# BatteryChargerCombiner.net
KiCad netlist of a schematic drawn in EAGLE
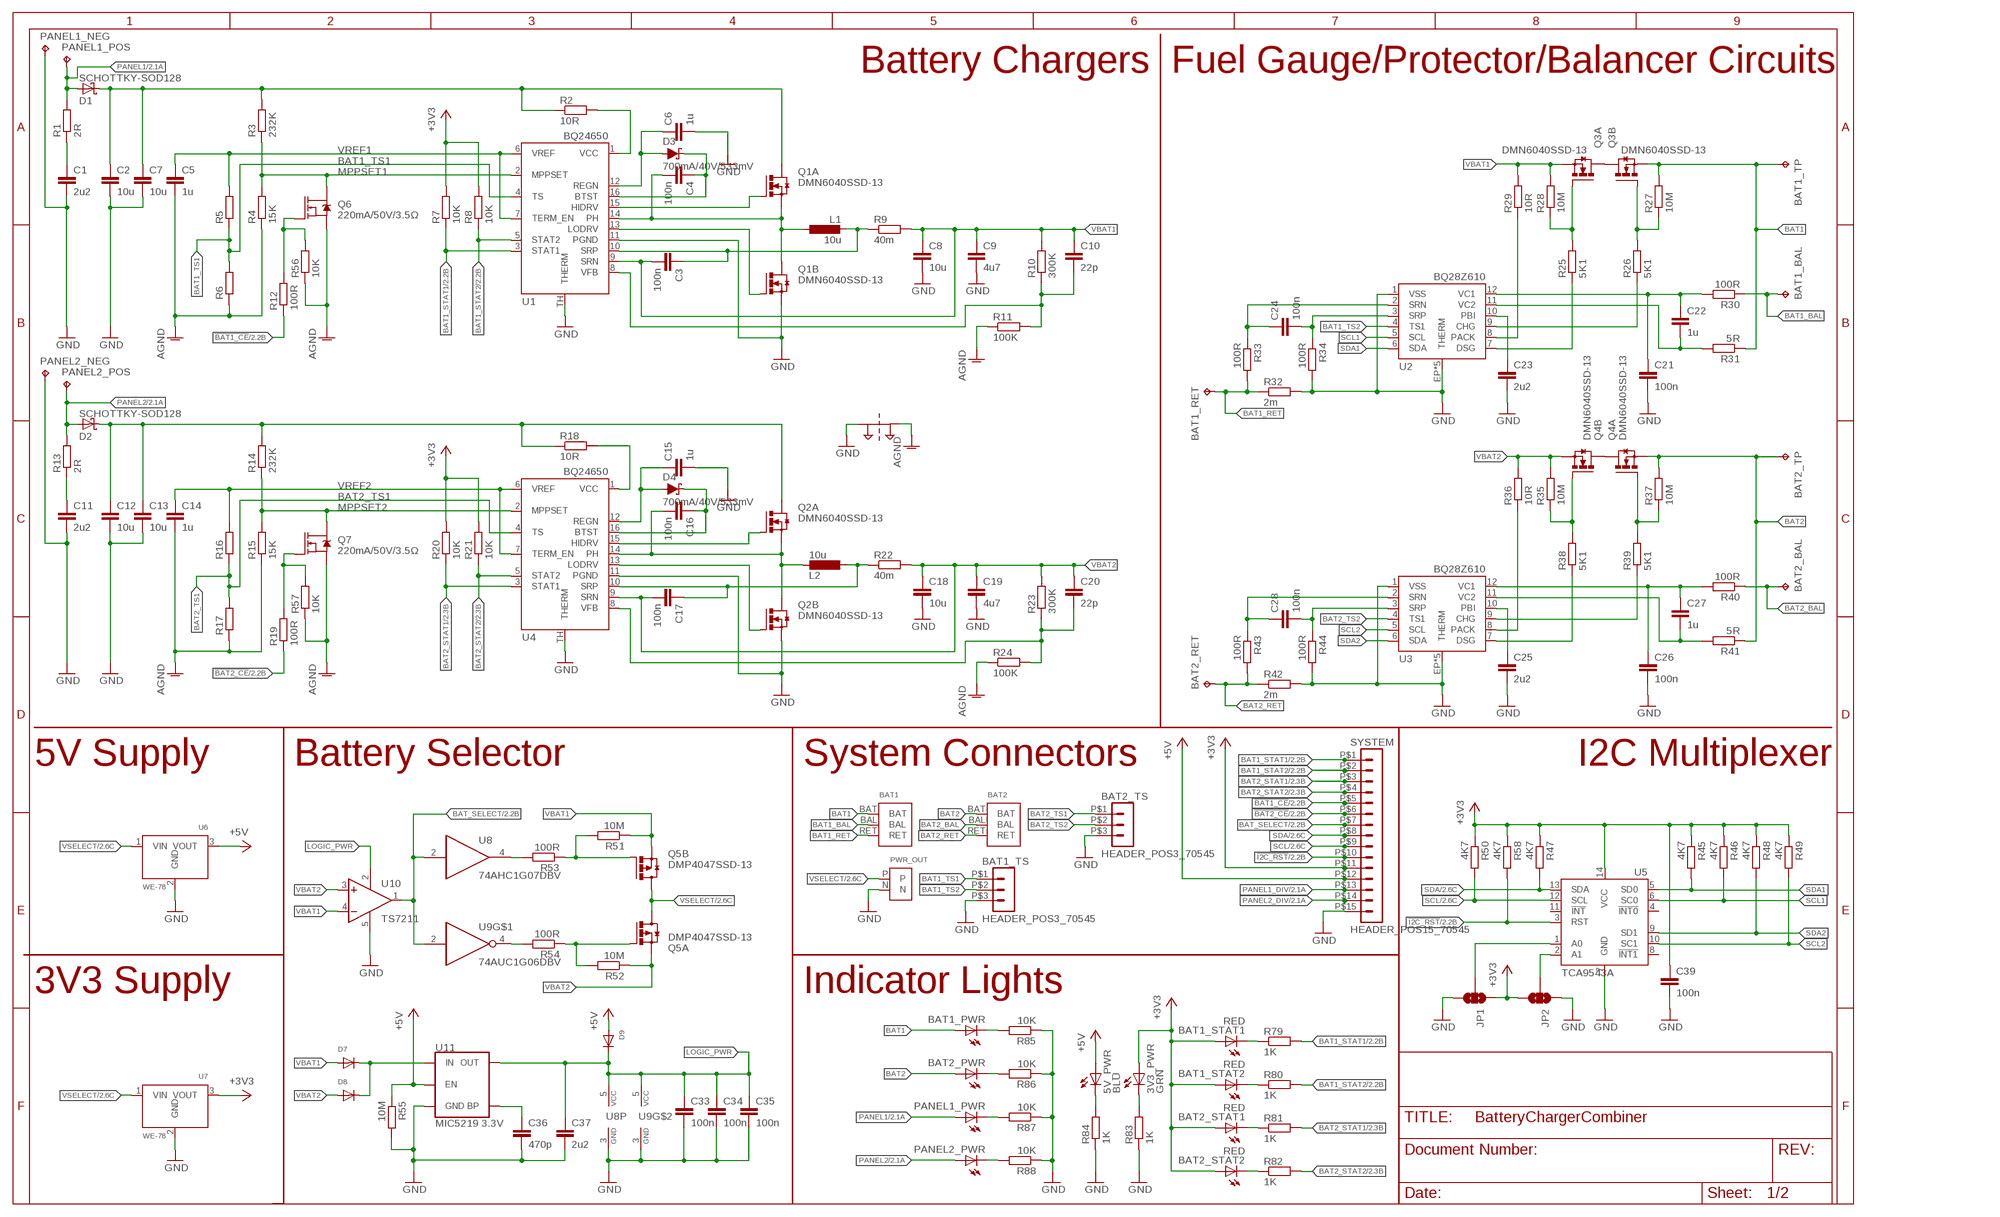
[diagram p0: schematic, sheet 1]
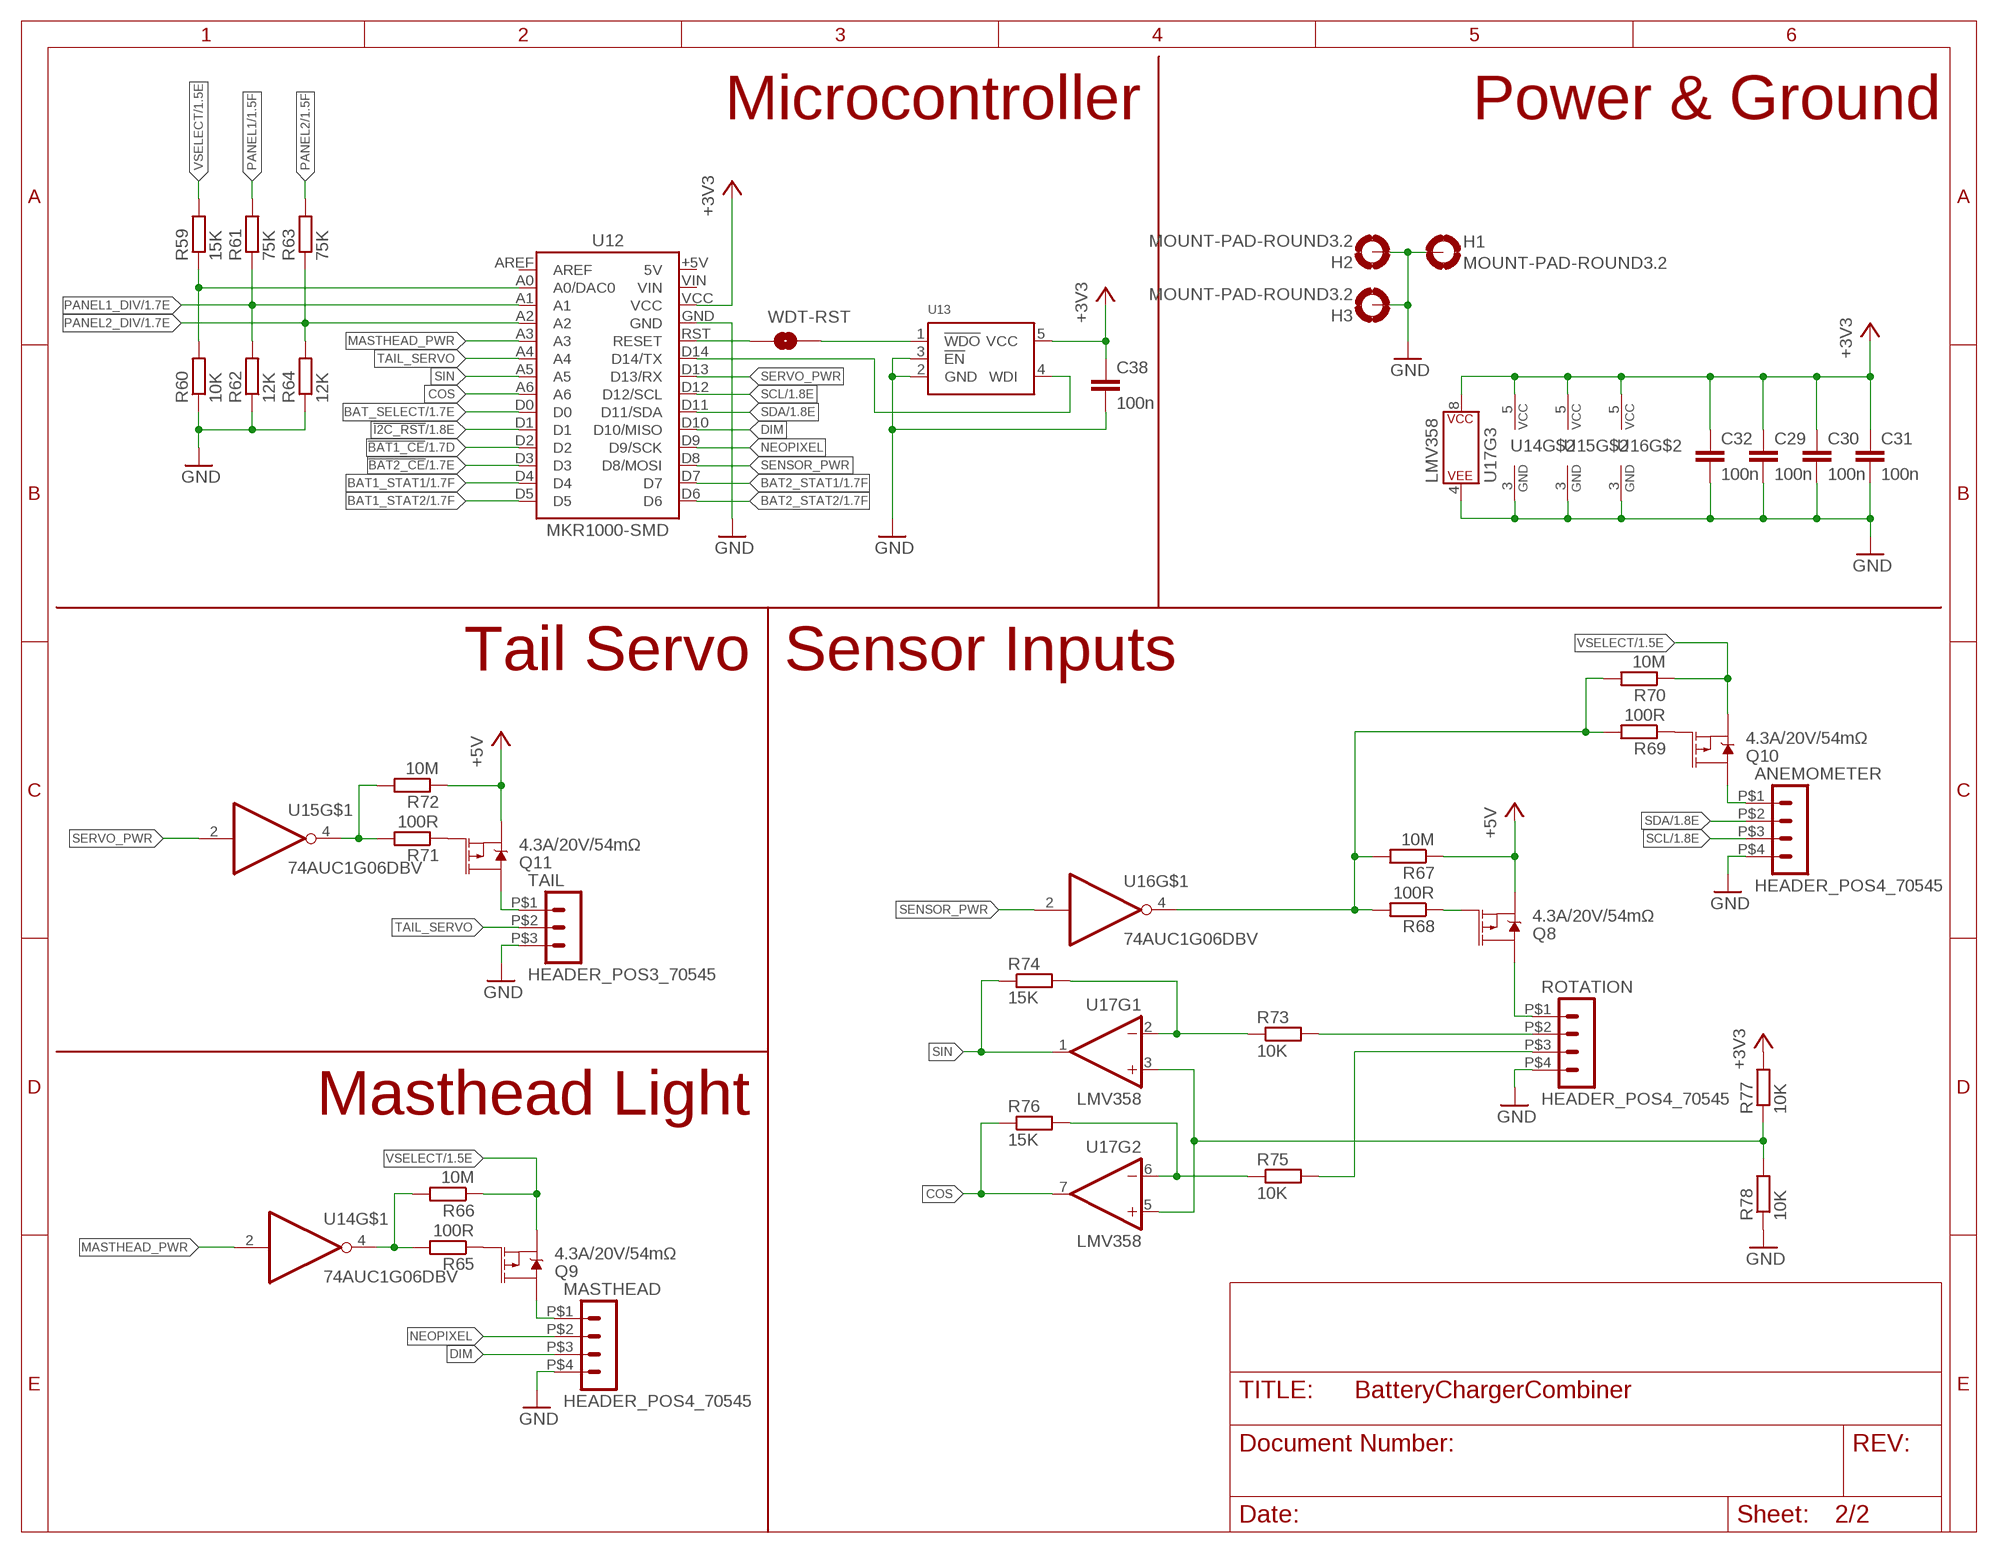
[diagram p1: schematic, sheet 2]

(export (version "E")
  (design (tool "Eeschema 10.0.6"))
  (components
    (comp (ref "ANEMOMETER")
      (value "HEADER_POS4_70545")
      (footprint "eagle-import:70545-POS4")
      (libsource (lib "eagle-import") (part "HEADER_POS4_?70545"))
    )
    (comp (ref "C29")
      (value "100n")
      (footprint "eagle-import:C0603")
      (libsource (lib "eagle-import") (part "C-EUC0603"))
    )
    (comp (ref "C30")
      (value "100n")
      (footprint "eagle-import:C0603")
      (libsource (lib "eagle-import") (part "C-EUC0603"))
    )
    (comp (ref "C31")
      (value "100n")
      (footprint "eagle-import:C0603")
      (libsource (lib "eagle-import") (part "C-EUC0603"))
    )
    (comp (ref "C32")
      (value "100n")
      (footprint "eagle-import:C0603")
      (libsource (lib "eagle-import") (part "C-EUC0603"))
    )
    (comp (ref "C38")
      (value "100n")
      (footprint "eagle-import:C0603")
      (libsource (lib "eagle-import") (part "C-EUC0603"))
    )
    (comp (ref "H1")
      (value "MOUNT-PAD-ROUND3.2")
      (footprint "eagle-import:3,2-PAD")
      (libsource (lib "eagle-import") (part "MOUNT-PAD-ROUND3.2"))
    )
    (comp (ref "H2")
      (value "MOUNT-PAD-ROUND3.2")
      (footprint "eagle-import:3,2-PAD")
      (libsource (lib "eagle-import") (part "MOUNT-PAD-ROUND3.2"))
    )
    (comp (ref "H3")
      (value "MOUNT-PAD-ROUND3.2")
      (footprint "eagle-import:3,2-PAD")
      (libsource (lib "eagle-import") (part "MOUNT-PAD-ROUND3.2"))
    )
    (comp (ref "MASTHEAD")
      (value "HEADER_POS4_70545")
      (footprint "eagle-import:70545-POS4")
      (libsource (lib "eagle-import") (part "HEADER_POS4_?70545"))
    )
    (comp (ref "Q8")
      (value "4.3A/20V/54mΩ")
      (footprint "eagle-import:SOT23-3")
      (libsource (lib "eagle-import") (part "MOSFET_PCH-IRLML2244"))
    )
    (comp (ref "Q9")
      (value "4.3A/20V/54mΩ")
      (footprint "eagle-import:SOT23-3")
      (libsource (lib "eagle-import") (part "MOSFET_PCH-IRLML2244"))
    )
    (comp (ref "Q10")
      (value "4.3A/20V/54mΩ")
      (footprint "eagle-import:SOT23-3")
      (libsource (lib "eagle-import") (part "MOSFET_PCH-IRLML2244"))
    )
    (comp (ref "Q11")
      (value "4.3A/20V/54mΩ")
      (footprint "eagle-import:SOT23-3")
      (libsource (lib "eagle-import") (part "MOSFET_PCH-IRLML2244"))
    )
    (comp (ref "R59")
      (value "15K")
      (footprint "eagle-import:R0603")
      (libsource (lib "eagle-import") (part "R-EU_R0603"))
    )
    (comp (ref "R60")
      (value "10K")
      (footprint "eagle-import:R0603")
      (libsource (lib "eagle-import") (part "R-EU_R0603"))
    )
    (comp (ref "R61")
      (value "75K")
      (footprint "eagle-import:R0603")
      (libsource (lib "eagle-import") (part "R-EU_R0603"))
    )
    (comp (ref "R62")
      (value "12K")
      (footprint "eagle-import:R0603")
      (libsource (lib "eagle-import") (part "R-EU_R0603"))
    )
    (comp (ref "R63")
      (value "75K")
      (footprint "eagle-import:R0603")
      (libsource (lib "eagle-import") (part "R-EU_R0603"))
    )
    (comp (ref "R64")
      (value "12K")
      (footprint "eagle-import:R0603")
      (libsource (lib "eagle-import") (part "R-EU_R0603"))
    )
    (comp (ref "R65")
      (value "100R")
      (footprint "eagle-import:R0603")
      (libsource (lib "eagle-import") (part "R-EU_R0603"))
    )
    (comp (ref "R66")
      (value "10M")
      (footprint "eagle-import:R0603")
      (libsource (lib "eagle-import") (part "R-EU_R0603"))
    )
    (comp (ref "R67")
      (value "10M")
      (footprint "eagle-import:R0603")
      (libsource (lib "eagle-import") (part "R-EU_R0603"))
    )
    (comp (ref "R68")
      (value "100R")
      (footprint "eagle-import:R0603")
      (libsource (lib "eagle-import") (part "R-EU_R0603"))
    )
    (comp (ref "R69")
      (value "100R")
      (footprint "eagle-import:R0603")
      (libsource (lib "eagle-import") (part "R-EU_R0603"))
    )
    (comp (ref "R70")
      (value "10M")
      (footprint "eagle-import:R0603")
      (libsource (lib "eagle-import") (part "R-EU_R0603"))
    )
    (comp (ref "R71")
      (value "100R")
      (footprint "eagle-import:R0603")
      (libsource (lib "eagle-import") (part "R-EU_R0603"))
    )
    (comp (ref "R72")
      (value "10M")
      (footprint "eagle-import:R0603")
      (libsource (lib "eagle-import") (part "R-EU_R0603"))
    )
    (comp (ref "R73")
      (value "10K")
      (footprint "eagle-import:R0603")
      (libsource (lib "eagle-import") (part "R-EU_R0603"))
    )
    (comp (ref "R74")
      (value "15K")
      (footprint "eagle-import:R0603")
      (libsource (lib "eagle-import") (part "R-EU_R0603"))
    )
    (comp (ref "R75")
      (value "10K")
      (footprint "eagle-import:R0603")
      (libsource (lib "eagle-import") (part "R-EU_R0603"))
    )
    (comp (ref "R76")
      (value "15K")
      (footprint "eagle-import:R0603")
      (libsource (lib "eagle-import") (part "R-EU_R0603"))
    )
    (comp (ref "R77")
      (value "10K")
      (footprint "eagle-import:R0603")
      (libsource (lib "eagle-import") (part "R-EU_R0603"))
    )
    (comp (ref "R78")
      (value "10K")
      (footprint "eagle-import:R0603")
      (libsource (lib "eagle-import") (part "R-EU_R0603"))
    )
    (comp (ref "ROTATION")
      (value "HEADER_POS4_70545")
      (footprint "eagle-import:70545-POS4")
      (libsource (lib "eagle-import") (part "HEADER_POS4_?70545"))
    )
    (comp (ref "TAIL")
      (value "HEADER_POS3_70545")
      (footprint "eagle-import:70545-POS3")
      (libsource (lib "eagle-import") (part "HEADER_POS3_?70545"))
    )
    (comp (ref "U12")
      (value "MKR1000-SMD")
      (footprint "eagle-import:MKR1000-SMD")
      (libsource (lib "eagle-import") (part "MKR1000-SMD"))
    )
    (comp (ref "U13")
      (value "STWD100")
      (footprint "eagle-import:DBV-R-PDSO-G5")
      (libsource (lib "eagle-import") (part "STWD100"))
    )
    (comp (ref "U14")
      (value "74AUC1G06DBV")
      (footprint "eagle-import:SOT23-5")
      (libsource (lib "eagle-import") (part "741G06DBVAUC"))
    )
    (comp (ref "U15")
      (value "74AUC1G06DBV")
      (footprint "eagle-import:SOT23-5")
      (libsource (lib "eagle-import") (part "741G06DBVAUC"))
    )
    (comp (ref "U16")
      (value "74AUC1G06DBV")
      (footprint "eagle-import:SOT23-5")
      (libsource (lib "eagle-import") (part "741G06DBVAUC"))
    )
    (comp (ref "U17")
      (value "LMV358")
      (footprint "eagle-import:SO08")
      (libsource (lib "eagle-import") (part "LMV358SOIC"))
    )
    (comp (ref "WDT-RST")
      (value "JUMPER-SMT_2_NO_SILK")
      (footprint "eagle-import:SMT-JUMPER_2_NO_SILK")
      (libsource (lib "eagle-import") (part "JUMPER-SMT_2_NO_SILK"))
    )
    (comp (ref "3V3_PWR")
      (value "GRN")
      (footprint "eagle-import:CHIP-LED0603")
      (libsource (lib "eagle-import") (part "LEDCHIP-LED0603"))
    )
    (comp (ref "5V_PWR")
      (value "BLU")
      (footprint "eagle-import:CHIP-LED0603")
      (libsource (lib "eagle-import") (part "LEDCHIP-LED0603"))
    )
    (comp (ref "BAT1")
      (value "2S-BATTERYSMD")
      (footprint "eagle-import:JST-XH3-SMD")
      (libsource (lib "eagle-import") (part "2S-BATTERYSMD"))
    )
    (comp (ref "BAT1_BAL")
      (value "TPPAD1-13Y")
      (footprint "eagle-import:P1-13Y")
      (libsource (lib "eagle-import") (part "TPPAD1-13Y"))
    )
    (comp (ref "BAT1_PWR")
      (value "LEDCHIP-LED0603")
      (footprint "eagle-import:CHIP-LED0603")
      (libsource (lib "eagle-import") (part "LEDCHIP-LED0603"))
    )
    (comp (ref "BAT1_RET")
      (value "TPPAD1-13Y")
      (footprint "eagle-import:P1-13Y")
      (libsource (lib "eagle-import") (part "TPPAD1-13Y"))
    )
    (comp (ref "BAT1_STAT1")
      (value "RED")
      (footprint "eagle-import:CHIP-LED0603")
      (libsource (lib "eagle-import") (part "LEDCHIP-LED0603"))
    )
    (comp (ref "BAT1_STAT2")
      (value "RED")
      (footprint "eagle-import:CHIP-LED0603")
      (libsource (lib "eagle-import") (part "LEDCHIP-LED0603"))
    )
    (comp (ref "BAT1_TP")
      (value "TPPAD1-13Y")
      (footprint "eagle-import:P1-13Y")
      (libsource (lib "eagle-import") (part "TPPAD1-13Y"))
    )
    (comp (ref "BAT1_TS")
      (value "HEADER_POS3_70545")
      (footprint "eagle-import:70545-POS3")
      (libsource (lib "eagle-import") (part "HEADER_POS3_?70545"))
    )
    (comp (ref "BAT2")
      (value "2S-BATTERYSMD")
      (footprint "eagle-import:JST-XH3-SMD")
      (libsource (lib "eagle-import") (part "2S-BATTERYSMD"))
    )
    (comp (ref "BAT2_BAL")
      (value "TPPAD1-13Y")
      (footprint "eagle-import:P1-13Y")
      (libsource (lib "eagle-import") (part "TPPAD1-13Y"))
    )
    (comp (ref "BAT2_PWR")
      (value "LEDCHIP-LED0603")
      (footprint "eagle-import:CHIP-LED0603")
      (libsource (lib "eagle-import") (part "LEDCHIP-LED0603"))
    )
    (comp (ref "BAT2_RET")
      (value "TPPAD1-13Y")
      (footprint "eagle-import:P1-13Y")
      (libsource (lib "eagle-import") (part "TPPAD1-13Y"))
    )
    (comp (ref "BAT2_STAT1")
      (value "RED")
      (footprint "eagle-import:CHIP-LED0603")
      (libsource (lib "eagle-import") (part "LEDCHIP-LED0603"))
    )
    (comp (ref "BAT2_STAT2")
      (value "RED")
      (footprint "eagle-import:CHIP-LED0603")
      (libsource (lib "eagle-import") (part "LEDCHIP-LED0603"))
    )
    (comp (ref "BAT2_TP")
      (value "TPPAD1-13Y")
      (footprint "eagle-import:P1-13Y")
      (libsource (lib "eagle-import") (part "TPPAD1-13Y"))
    )
    (comp (ref "BAT2_TS")
      (value "HEADER_POS3_70545")
      (footprint "eagle-import:70545-POS3")
      (libsource (lib "eagle-import") (part "HEADER_POS3_?70545"))
    )
    (comp (ref "C1")
      (value "2u2")
      (footprint "eagle-import:C0603")
      (libsource (lib "eagle-import") (part "C-EUC0603"))
    )
    (comp (ref "C2")
      (value "10u")
      (footprint "eagle-import:C1210")
      (libsource (lib "eagle-import") (part "C-EUC1210"))
    )
    (comp (ref "C3")
      (value "100n")
      (footprint "eagle-import:C0603")
      (libsource (lib "eagle-import") (part "C-EUC0603"))
    )
    (comp (ref "C4")
      (value "100n")
      (footprint "eagle-import:C0603")
      (libsource (lib "eagle-import") (part "C-EUC0603"))
    )
    (comp (ref "C5")
      (value "1u")
      (footprint "eagle-import:C0603")
      (libsource (lib "eagle-import") (part "C-EUC0603"))
    )
    (comp (ref "C6")
      (value "1u")
      (footprint "eagle-import:C0603")
      (libsource (lib "eagle-import") (part "C-EUC0603"))
    )
    (comp (ref "C7")
      (value "10u")
      (footprint "eagle-import:C1210")
      (libsource (lib "eagle-import") (part "C-EUC1210"))
    )
    (comp (ref "C8")
      (value "10u")
      (footprint "eagle-import:C1210")
      (libsource (lib "eagle-import") (part "C-EUC1210"))
    )
    (comp (ref "C9")
      (value "4u7")
      (footprint "eagle-import:C1210")
      (libsource (lib "eagle-import") (part "C-EUC1210"))
    )
    (comp (ref "C10")
      (value "22p")
      (footprint "eagle-import:C0603")
      (libsource (lib "eagle-import") (part "C-EUC0603"))
    )
    (comp (ref "C11")
      (value "2u2")
      (footprint "eagle-import:C0603")
      (libsource (lib "eagle-import") (part "C-EUC0603"))
    )
    (comp (ref "C12")
      (value "10u")
      (footprint "eagle-import:C1210")
      (libsource (lib "eagle-import") (part "C-EUC1210"))
    )
    (comp (ref "C13")
      (value "10u")
      (footprint "eagle-import:C1210")
      (libsource (lib "eagle-import") (part "C-EUC1210"))
    )
    (comp (ref "C14")
      (value "1u")
      (footprint "eagle-import:C0603")
      (libsource (lib "eagle-import") (part "C-EUC0603"))
    )
    (comp (ref "C15")
      (value "1u")
      (footprint "eagle-import:C0603")
      (libsource (lib "eagle-import") (part "C-EUC0603"))
    )
    (comp (ref "C16")
      (value "100n")
      (footprint "eagle-import:C0603")
      (libsource (lib "eagle-import") (part "C-EUC0603"))
    )
    (comp (ref "C17")
      (value "100n")
      (footprint "eagle-import:C0603")
      (libsource (lib "eagle-import") (part "C-EUC0603"))
    )
    (comp (ref "C18")
      (value "10u")
      (footprint "eagle-import:C1210")
      (libsource (lib "eagle-import") (part "C-EUC1210"))
    )
    (comp (ref "C19")
      (value "4u7")
      (footprint "eagle-import:C1210")
      (libsource (lib "eagle-import") (part "C-EUC1210"))
    )
    (comp (ref "C20")
      (value "22p")
      (footprint "eagle-import:C0603")
      (libsource (lib "eagle-import") (part "C-EUC0603"))
    )
    (comp (ref "C21")
      (value "100n")
      (footprint "eagle-import:C0603")
      (libsource (lib "eagle-import") (part "C-EUC0603"))
    )
    (comp (ref "C22")
      (value "1u")
      (footprint "eagle-import:C0603")
      (libsource (lib "eagle-import") (part "C-EUC0603"))
    )
    (comp (ref "C23")
      (value "2u2")
      (footprint "eagle-import:C0603")
      (libsource (lib "eagle-import") (part "C-EUC0603"))
    )
    (comp (ref "C24")
      (value "100n")
      (footprint "eagle-import:C0603")
      (libsource (lib "eagle-import") (part "C-EUC0603"))
    )
    (comp (ref "C25")
      (value "2u2")
      (footprint "eagle-import:C0603")
      (libsource (lib "eagle-import") (part "C-EUC0603"))
    )
    (comp (ref "C26")
      (value "100n")
      (footprint "eagle-import:C0603")
      (libsource (lib "eagle-import") (part "C-EUC0603"))
    )
    (comp (ref "C27")
      (value "1u")
      (footprint "eagle-import:C0603")
      (libsource (lib "eagle-import") (part "C-EUC0603"))
    )
    (comp (ref "C28")
      (value "100n")
      (footprint "eagle-import:C0603")
      (libsource (lib "eagle-import") (part "C-EUC0603"))
    )
    (comp (ref "C33")
      (value "100n")
      (footprint "eagle-import:C0603")
      (libsource (lib "eagle-import") (part "C-EUC0603"))
    )
    (comp (ref "C34")
      (value "100n")
      (footprint "eagle-import:C0603")
      (libsource (lib "eagle-import") (part "C-EUC0603"))
    )
    (comp (ref "C35")
      (value "100n")
      (footprint "eagle-import:C0603")
      (libsource (lib "eagle-import") (part "C-EUC0603"))
    )
    (comp (ref "C36")
      (value "470p")
      (footprint "eagle-import:C0603")
      (libsource (lib "eagle-import") (part "C-EUC0603"))
    )
    (comp (ref "C37")
      (value "2u2")
      (footprint "eagle-import:C0603")
      (libsource (lib "eagle-import") (part "C-EUC0603"))
    )
    (comp (ref "C39")
      (value "100n")
      (footprint "eagle-import:C0603")
      (libsource (lib "eagle-import") (part "C-EUC0603"))
    )
    (comp (ref "D1")
      (value "SCHOTTKY-SOD128")
      (footprint "eagle-import:SOD-128")
      (libsource (lib "eagle-import") (part "SCHOTTKY-SOD128"))
    )
    (comp (ref "D2")
      (value "SCHOTTKY-SOD128")
      (footprint "eagle-import:SOD-128")
      (libsource (lib "eagle-import") (part "SCHOTTKY-SOD128"))
    )
    (comp (ref "D3")
      (value "700mA/40V/533mV")
      (footprint "eagle-import:SOT23-3")
      (libsource (lib "eagle-import") (part "DIODE-SCHOTTKY-ZLLS500"))
    )
    (comp (ref "D4")
      (value "700mA/40V/533mV")
      (footprint "eagle-import:SOT23-3")
      (libsource (lib "eagle-import") (part "DIODE-SCHOTTKY-ZLLS500"))
    )
    (comp (ref "D7")
      (value "DIODESOD-123")
      (footprint "eagle-import:SOD-123")
      (libsource (lib "eagle-import") (part "DIODESOD-123"))
    )
    (comp (ref "D8")
      (value "DIODESOD-123")
      (footprint "eagle-import:SOD-123")
      (libsource (lib "eagle-import") (part "DIODESOD-123"))
    )
    (comp (ref "D9")
      (value "DIODESOD-123")
      (footprint "eagle-import:SOD-123")
      (libsource (lib "eagle-import") (part "DIODESOD-123"))
    )
    (comp (ref "JP1")
      (value "JUMPER-SMT_3_NO_SILK")
      (footprint "eagle-import:SMT-JUMPER_3_NO_SILK")
      (libsource (lib "eagle-import") (part "JUMPER-SMT_3_NO_SILK"))
    )
    (comp (ref "JP2")
      (value "JUMPER-SMT_3_NO_SILK")
      (footprint "eagle-import:SMT-JUMPER_3_NO_SILK")
      (libsource (lib "eagle-import") (part "JUMPER-SMT_3_NO_SILK"))
    )
    (comp (ref "L1")
      (value "10u")
      (footprint "eagle-import:DG6050")
      (libsource (lib "eagle-import") (part "INDUCTOR-DG6050"))
    )
    (comp (ref "L2")
      (value "10u")
      (footprint "eagle-import:DG6050")
      (libsource (lib "eagle-import") (part "INDUCTOR-DG6050"))
    )
    (comp (ref "PANEL1_NEG")
      (value "TPPAD1-13Y")
      (footprint "eagle-import:P1-13Y")
      (libsource (lib "eagle-import") (part "TPPAD1-13Y"))
    )
    (comp (ref "PANEL1_POS")
      (value "TPPAD1-13Y")
      (footprint "eagle-import:P1-13Y")
      (libsource (lib "eagle-import") (part "TPPAD1-13Y"))
    )
    (comp (ref "PANEL1_PWR")
      (value "LEDCHIP-LED0603")
      (footprint "eagle-import:CHIP-LED0603")
      (libsource (lib "eagle-import") (part "LEDCHIP-LED0603"))
    )
    (comp (ref "PANEL2_NEG")
      (value "TPPAD1-13Y")
      (footprint "eagle-import:P1-13Y")
      (libsource (lib "eagle-import") (part "TPPAD1-13Y"))
    )
    (comp (ref "PANEL2_POS")
      (value "TPPAD1-13Y")
      (footprint "eagle-import:P1-13Y")
      (libsource (lib "eagle-import") (part "TPPAD1-13Y"))
    )
    (comp (ref "PANEL2_PWR")
      (value "LEDCHIP-LED0603")
      (footprint "eagle-import:CHIP-LED0603")
      (libsource (lib "eagle-import") (part "LEDCHIP-LED0603"))
    )
    (comp (ref "PWR_OUT")
      (value "PWR")
      (footprint "eagle-import:JST-XH2-THRUHOLE")
      (libsource (lib "eagle-import") (part "PWR"))
    )
    (comp (ref "Q1")
      (value "DMN6040SSD-13")
      (footprint "eagle-import:SO-08")
      (libsource (lib "eagle-import") (part "IRF8313P"))
    )
    (comp (ref "Q2")
      (value "DMN6040SSD-13")
      (footprint "eagle-import:SO-08")
      (libsource (lib "eagle-import") (part "IRF8313P"))
    )
    (comp (ref "Q3")
      (value "DMN6040SSD-13")
      (footprint "eagle-import:SO-08")
      (libsource (lib "eagle-import") (part "IRF8313P"))
    )
    (comp (ref "Q4")
      (value "DMN6040SSD-13")
      (footprint "eagle-import:SO-08")
      (libsource (lib "eagle-import") (part "IRF8313P"))
    )
    (comp (ref "Q5")
      (value "DMP4047SSD-13")
      (footprint "eagle-import:SO08")
      (libsource (lib "eagle-import") (part "DMP4047SSD-13"))
    )
    (comp (ref "Q6")
      (value "220mA/50V/3.5Ω")
      (footprint "eagle-import:SOT23-3")
      (libsource (lib "eagle-import") (part "MOSFET-NCH-BSS138"))
    )
    (comp (ref "Q7")
      (value "220mA/50V/3.5Ω")
      (footprint "eagle-import:SOT23-3")
      (libsource (lib "eagle-import") (part "MOSFET-NCH-BSS138"))
    )
    (comp (ref "R1")
      (value "2R")
      (footprint "eagle-import:R0603")
      (libsource (lib "eagle-import") (part "R-EU_R0603"))
    )
    (comp (ref "R2")
      (value "10R")
      (footprint "eagle-import:R1206")
      (libsource (lib "eagle-import") (part "R-EU_R1206"))
    )
    (comp (ref "R3")
      (value "232K")
      (footprint "eagle-import:R0603")
      (libsource (lib "eagle-import") (part "R-EU_R0603"))
    )
    (comp (ref "R4")
      (value "15K")
      (footprint "eagle-import:R0603")
      (libsource (lib "eagle-import") (part "R-EU_R0603"))
    )
    (comp (ref "R5")
      (value "R-EU_R0603")
      (footprint "eagle-import:R0603")
      (libsource (lib "eagle-import") (part "R-EU_R0603"))
    )
    (comp (ref "R6")
      (value "R-EU_R0603")
      (footprint "eagle-import:R0603")
      (libsource (lib "eagle-import") (part "R-EU_R0603"))
    )
    (comp (ref "R7")
      (value "10K")
      (footprint "eagle-import:R0603")
      (libsource (lib "eagle-import") (part "R-EU_R0603"))
    )
    (comp (ref "R8")
      (value "10K")
      (footprint "eagle-import:R0603")
      (libsource (lib "eagle-import") (part "R-EU_R0603"))
    )
    (comp (ref "R9")
      (value "40m")
      (footprint "eagle-import:R2512")
      (libsource (lib "eagle-import") (part "R-EU_R2512"))
    )
    (comp (ref "R10")
      (value "300K")
      (footprint "eagle-import:R0603")
      (libsource (lib "eagle-import") (part "R-EU_R0603"))
    )
    (comp (ref "R11")
      (value "100K")
      (footprint "eagle-import:R0603")
      (libsource (lib "eagle-import") (part "R-EU_R0603"))
    )
    (comp (ref "R12")
      (value "100R")
      (footprint "eagle-import:R0603")
      (libsource (lib "eagle-import") (part "R-EU_R0603"))
    )
    (comp (ref "R13")
      (value "2R")
      (footprint "eagle-import:R0603")
      (libsource (lib "eagle-import") (part "R-EU_R0603"))
    )
    (comp (ref "R14")
      (value "232K")
      (footprint "eagle-import:R0603")
      (libsource (lib "eagle-import") (part "R-EU_R0603"))
    )
    (comp (ref "R15")
      (value "15K")
      (footprint "eagle-import:R0603")
      (libsource (lib "eagle-import") (part "R-EU_R0603"))
    )
    (comp (ref "R16")
      (value "R-EU_R0603")
      (footprint "eagle-import:R0603")
      (libsource (lib "eagle-import") (part "R-EU_R0603"))
    )
    (comp (ref "R17")
      (value "R-EU_R0603")
      (footprint "eagle-import:R0603")
      (libsource (lib "eagle-import") (part "R-EU_R0603"))
    )
    (comp (ref "R18")
      (value "10R")
      (footprint "eagle-import:R1206")
      (libsource (lib "eagle-import") (part "R-EU_R1206"))
    )
    (comp (ref "R19")
      (value "100R")
      (footprint "eagle-import:R0603")
      (libsource (lib "eagle-import") (part "R-EU_R0603"))
    )
    (comp (ref "R20")
      (value "10K")
      (footprint "eagle-import:R0603")
      (libsource (lib "eagle-import") (part "R-EU_R0603"))
    )
    (comp (ref "R21")
      (value "10K")
      (footprint "eagle-import:R0603")
      (libsource (lib "eagle-import") (part "R-EU_R0603"))
    )
    (comp (ref "R22")
      (value "40m")
      (footprint "eagle-import:R2512")
      (libsource (lib "eagle-import") (part "R-EU_R2512"))
    )
    (comp (ref "R23")
      (value "300K")
      (footprint "eagle-import:R0603")
      (libsource (lib "eagle-import") (part "R-EU_R0603"))
    )
    (comp (ref "R24")
      (value "100K")
      (footprint "eagle-import:R0603")
      (libsource (lib "eagle-import") (part "R-EU_R0603"))
    )
    (comp (ref "R25")
      (value "5K1")
      (footprint "eagle-import:R0603")
      (libsource (lib "eagle-import") (part "R-EU_R0603"))
    )
    (comp (ref "R26")
      (value "5K1")
      (footprint "eagle-import:R0603")
      (libsource (lib "eagle-import") (part "R-EU_R0603"))
    )
    (comp (ref "R27")
      (value "10M")
      (footprint "eagle-import:R0603")
      (libsource (lib "eagle-import") (part "R-EU_R0603"))
    )
    (comp (ref "R28")
      (value "10M")
      (footprint "eagle-import:R0603")
      (libsource (lib "eagle-import") (part "R-EU_R0603"))
    )
    (comp (ref "R29")
      (value "10R")
      (footprint "eagle-import:R0603")
      (libsource (lib "eagle-import") (part "R-EU_R0603"))
    )
    (comp (ref "R30")
      (value "100R")
      (footprint "eagle-import:R0603")
      (libsource (lib "eagle-import") (part "R-EU_R0603"))
    )
    (comp (ref "R31")
      (value "5R")
      (footprint "eagle-import:R0603")
      (libsource (lib "eagle-import") (part "R-EU_R0603"))
    )
    (comp (ref "R32")
      (value "2m")
      (footprint "eagle-import:R2512")
      (libsource (lib "eagle-import") (part "R-EU_R2512"))
    )
    (comp (ref "R33")
      (value "100R")
      (footprint "eagle-import:R0603")
      (libsource (lib "eagle-import") (part "R-EU_R0603"))
    )
    (comp (ref "R34")
      (value "100R")
      (footprint "eagle-import:R0603")
      (libsource (lib "eagle-import") (part "R-EU_R0603"))
    )
    (comp (ref "R35")
      (value "10M")
      (footprint "eagle-import:R0603")
      (libsource (lib "eagle-import") (part "R-EU_R0603"))
    )
    (comp (ref "R36")
      (value "10R")
      (footprint "eagle-import:R0603")
      (libsource (lib "eagle-import") (part "R-EU_R0603"))
    )
    (comp (ref "R37")
      (value "10M")
      (footprint "eagle-import:R0603")
      (libsource (lib "eagle-import") (part "R-EU_R0603"))
    )
    (comp (ref "R38")
      (value "5K1")
      (footprint "eagle-import:R0603")
      (libsource (lib "eagle-import") (part "R-EU_R0603"))
    )
    (comp (ref "R39")
      (value "5K1")
      (footprint "eagle-import:R0603")
      (libsource (lib "eagle-import") (part "R-EU_R0603"))
    )
    (comp (ref "R40")
      (value "100R")
      (footprint "eagle-import:R0603")
      (libsource (lib "eagle-import") (part "R-EU_R0603"))
    )
    (comp (ref "R41")
      (value "5R")
      (footprint "eagle-import:R0603")
      (libsource (lib "eagle-import") (part "R-EU_R0603"))
    )
    (comp (ref "R42")
      (value "2m")
      (footprint "eagle-import:R2512")
      (libsource (lib "eagle-import") (part "R-EU_R2512"))
    )
    (comp (ref "R43")
      (value "100R")
      (footprint "eagle-import:R0603")
      (libsource (lib "eagle-import") (part "R-EU_R0603"))
    )
    (comp (ref "R44")
      (value "100R")
      (footprint "eagle-import:R0603")
      (libsource (lib "eagle-import") (part "R-EU_R0603"))
    )
    (comp (ref "R45")
      (value "4K7")
      (footprint "eagle-import:R0603")
      (libsource (lib "eagle-import") (part "R-EU_R0603"))
    )
    (comp (ref "R46")
      (value "4K7")
      (footprint "eagle-import:R0603")
      (libsource (lib "eagle-import") (part "R-EU_R0603"))
    )
    (comp (ref "R47")
      (value "4K7")
      (footprint "eagle-import:R0603")
      (libsource (lib "eagle-import") (part "R-EU_R0603"))
    )
    (comp (ref "R48")
      (value "4K7")
      (footprint "eagle-import:R0603")
      (libsource (lib "eagle-import") (part "R-EU_R0603"))
    )
    (comp (ref "R49")
      (value "4K7")
      (footprint "eagle-import:R0603")
      (libsource (lib "eagle-import") (part "R-EU_R0603"))
    )
    (comp (ref "R50")
      (value "4K7")
      (footprint "eagle-import:R0603")
      (libsource (lib "eagle-import") (part "R-EU_R0603"))
    )
    (comp (ref "R51")
      (value "10M")
      (footprint "eagle-import:R0603")
      (libsource (lib "eagle-import") (part "R-EU_R0603"))
    )
    (comp (ref "R52")
      (value "10M")
      (footprint "eagle-import:R0603")
      (libsource (lib "eagle-import") (part "R-EU_R0603"))
    )
    (comp (ref "R53")
      (value "100R")
      (footprint "eagle-import:R0603")
      (libsource (lib "eagle-import") (part "R-EU_R0603"))
    )
    (comp (ref "R54")
      (value "100R")
      (footprint "eagle-import:R0603")
      (libsource (lib "eagle-import") (part "R-EU_R0603"))
    )
    (comp (ref "R55")
      (value "10M")
      (footprint "eagle-import:R0603")
      (libsource (lib "eagle-import") (part "R-EU_R0603"))
    )
    (comp (ref "R56")
      (value "10K")
      (footprint "eagle-import:R0603")
      (libsource (lib "eagle-import") (part "R-EU_R0603"))
    )
    (comp (ref "R57")
      (value "10K")
      (footprint "eagle-import:R0603")
      (libsource (lib "eagle-import") (part "R-EU_R0603"))
    )
    (comp (ref "R58")
      (value "4K7")
      (footprint "eagle-import:R0603")
      (libsource (lib "eagle-import") (part "R-EU_R0603"))
    )
    (comp (ref "R79")
      (value "1K")
      (footprint "eagle-import:R0603")
      (libsource (lib "eagle-import") (part "R-EU_R0603"))
    )
    (comp (ref "R80")
      (value "1K")
      (footprint "eagle-import:R0603")
      (libsource (lib "eagle-import") (part "R-EU_R0603"))
    )
    (comp (ref "R81")
      (value "1K")
      (footprint "eagle-import:R0603")
      (libsource (lib "eagle-import") (part "R-EU_R0603"))
    )
    (comp (ref "R82")
      (value "1K")
      (footprint "eagle-import:R0603")
      (libsource (lib "eagle-import") (part "R-EU_R0603"))
    )
    (comp (ref "R83")
      (value "1K")
      (footprint "eagle-import:R0603")
      (libsource (lib "eagle-import") (part "R-EU_R0603"))
    )
    (comp (ref "R84")
      (value "1K")
      (footprint "eagle-import:R0603")
      (libsource (lib "eagle-import") (part "R-EU_R0603"))
    )
    (comp (ref "R85")
      (value "10K")
      (footprint "eagle-import:R0603")
      (libsource (lib "eagle-import") (part "R-EU_R0603"))
    )
    (comp (ref "R86")
      (value "10K")
      (footprint "eagle-import:R0603")
      (libsource (lib "eagle-import") (part "R-EU_R0603"))
    )
    (comp (ref "R87")
      (value "10K")
      (footprint "eagle-import:R0603")
      (libsource (lib "eagle-import") (part "R-EU_R0603"))
    )
    (comp (ref "R88")
      (value "10K")
      (footprint "eagle-import:R0603")
      (libsource (lib "eagle-import") (part "R-EU_R0603"))
    )
    (comp (ref "SUPPLY1")
      (value "2PT_GND_TIE")
      (footprint "eagle-import:2PT_GND_TIE")
      (libsource (lib "eagle-import") (part "2PT_GND_TIE"))
    )
    (comp (ref "SYSTEM")
      (value "HEADER_POS15_70545")
      (footprint "eagle-import:70545-POS15")
      (libsource (lib "eagle-import") (part "HEADER_POS15_?70545"))
    )
    (comp (ref "U1")
      (value "BQ24650")
      (footprint "eagle-import:QFN16")
      (libsource (lib "eagle-import") (part "BQ24650"))
    )
    (comp (ref "U2")
      (value "BQ28Z610")
      (footprint "eagle-import:PDSO-N12")
      (libsource (lib "eagle-import") (part "BQ28Z610"))
    )
    (comp (ref "U3")
      (value "BQ28Z610")
      (footprint "eagle-import:PDSO-N12")
      (libsource (lib "eagle-import") (part "BQ28Z610"))
    )
    (comp (ref "U4")
      (value "BQ24650")
      (footprint "eagle-import:QFN16")
      (libsource (lib "eagle-import") (part "BQ24650"))
    )
    (comp (ref "U5")
      (value "TCA9543A")
      (footprint "eagle-import:SO-14")
      (libsource (lib "eagle-import") (part "TCA9543A"))
    )
    (comp (ref "U6")
      (value "WE-78")
      (footprint "eagle-import:WE-78")
      (libsource (lib "eagle-import") (part "WE-78"))
    )
    (comp (ref "U7")
      (value "WE-78")
      (footprint "eagle-import:WE-78")
      (libsource (lib "eagle-import") (part "WE-78"))
    )
    (comp (ref "U8")
      (value "74AHC1G07DBV")
      (footprint "eagle-import:SOT23-5")
      (libsource (lib "eagle-import") (part "741G07DBVAHC"))
    )
    (comp (ref "U9")
      (value "74AUC1G06DBV")
      (footprint "eagle-import:SOT23-5")
      (libsource (lib "eagle-import") (part "741G06DBVAUC"))
    )
    (comp (ref "U10")
      (value "TS7211")
      (footprint "eagle-import:DBV-R-PDSO-G5")
      (libsource (lib "eagle-import") (part "TS7211"))
    )
    (comp (ref "U11")
      (value "MIC5219 3.3V")
      (footprint "eagle-import:SOT23-5")
      (libsource (lib "eagle-import") (part "V_REG_MIC52193.3V"))
    )
  )
  (nets
    (net (code "1") (name "+3V3") (class "Default")
      (node (ref "3V3_PWR") (pin "A") (pinfunction "A_A") (pintype "passive"))
      (node (ref "BAT1_STAT1") (pin "A") (pinfunction "A_A") (pintype "passive"))
      (node (ref "BAT1_STAT2") (pin "A") (pinfunction "A_A") (pintype "passive"))
      (node (ref "BAT2_STAT1") (pin "A") (pinfunction "A_A") (pintype "passive"))
      (node (ref "BAT2_STAT2") (pin "A") (pinfunction "A_A") (pintype "passive"))
      (node (ref "C29") (pin "1") (pinfunction "1_1") (pintype "passive"))
      (node (ref "C30") (pin "1") (pinfunction "1_1") (pintype "passive"))
      (node (ref "C31") (pin "1") (pinfunction "1_1") (pintype "passive"))
      (node (ref "C32") (pin "1") (pinfunction "1_1") (pintype "passive"))
      (node (ref "C38") (pin "1") (pinfunction "1_1") (pintype "passive"))
      (node (ref "C39") (pin "1") (pinfunction "1_1") (pintype "passive"))
      (node (ref "JP1") (pin "1") (pinfunction "1_1") (pintype "passive"))
      (node (ref "JP2") (pin "3") (pinfunction "3_3") (pintype "passive"))
      (node (ref "R20") (pin "2") (pinfunction "2_2") (pintype "passive"))
      (node (ref "R21") (pin "2") (pinfunction "2_2") (pintype "passive"))
      (node (ref "R45") (pin "1") (pinfunction "1_1") (pintype "passive"))
      (node (ref "R46") (pin "1") (pinfunction "1_1") (pintype "passive"))
      (node (ref "R47") (pin "1") (pinfunction "1_1") (pintype "passive"))
      (node (ref "R48") (pin "1") (pinfunction "1_1") (pintype "passive"))
      (node (ref "R49") (pin "1") (pinfunction "1_1") (pintype "passive"))
      (node (ref "R50") (pin "1") (pinfunction "1_1") (pintype "passive"))
      (node (ref "R58") (pin "1") (pinfunction "1_1") (pintype "passive"))
      (node (ref "R7") (pin "2") (pinfunction "2_2") (pintype "passive"))
      (node (ref "R77") (pin "2") (pinfunction "2_2") (pintype "passive"))
      (node (ref "R8") (pin "2") (pinfunction "2_2") (pintype "passive"))
      (node (ref "SYSTEM") (pin "P$11") (pinfunction "11_P$11") (pintype "passive"))
      (node (ref "U12") (pin "VCC") (pinfunction "VCC_VCC") (pintype "bidirectional"))
      (node (ref "U13") (pin "5") (pinfunction "VCC_5") (pintype "bidirectional"))
      (node (ref "U14") (pin "5") (pinfunction "VCC_5") (pintype "power_in"))
      (node (ref "U15") (pin "5") (pinfunction "VCC_5") (pintype "power_in"))
      (node (ref "U16") (pin "5") (pinfunction "VCC_5") (pintype "power_in"))
      (node (ref "U17") (pin "8") (pinfunction "P$V+_8") (pintype "bidirectional"))
      (node (ref "U5") (pin "14") (pinfunction "VCC_14") (pintype "bidirectional"))
      (node (ref "U7") (pin "3") (pinfunction "VOUT_3") (pintype "bidirectional"))
    )
    (net (code "2") (name "+5V") (class "Default")
      (node (ref "5V_PWR") (pin "A") (pinfunction "A_A") (pintype "passive"))
      (node (ref "D9") (pin "A") (pinfunction "A_A") (pintype "passive"))
      (node (ref "Q11") (pin "2") (pinfunction "S_2") (pintype "bidirectional"))
      (node (ref "Q8") (pin "2") (pinfunction "S_2") (pintype "bidirectional"))
      (node (ref "R55") (pin "1") (pinfunction "1_1") (pintype "passive"))
      (node (ref "R67") (pin "1") (pinfunction "1_1") (pintype "passive"))
      (node (ref "R72") (pin "1") (pinfunction "1_1") (pintype "passive"))
      (node (ref "SYSTEM") (pin "P$12") (pinfunction "12_P$12") (pintype "passive"))
      (node (ref "U11") (pin "3") (pinfunction "EN_3") (pintype "input"))
      (node (ref "U6") (pin "3") (pinfunction "VOUT_3") (pintype "bidirectional"))
    )
    (net (code "3") (name "AGND") (class "Default")
      (node (ref "C14") (pin "2") (pinfunction "2_2") (pintype "passive"))
      (node (ref "C5") (pin "2") (pinfunction "2_2") (pintype "passive"))
      (node (ref "Q6") (pin "2") (pinfunction "S_2") (pintype "bidirectional"))
      (node (ref "Q7") (pin "2") (pinfunction "S_2") (pintype "bidirectional"))
      (node (ref "R11") (pin "1") (pinfunction "1_1") (pintype "passive"))
      (node (ref "R15") (pin "1") (pinfunction "1_1") (pintype "passive"))
      (node (ref "R17") (pin "1") (pinfunction "1_1") (pintype "passive"))
      (node (ref "R24") (pin "1") (pinfunction "1_1") (pintype "passive"))
      (node (ref "R4") (pin "1") (pinfunction "1_1") (pintype "passive"))
      (node (ref "R56") (pin "1") (pinfunction "1_1") (pintype "passive"))
      (node (ref "R57") (pin "1") (pinfunction "1_1") (pintype "passive"))
      (node (ref "R6") (pin "1") (pinfunction "1_1") (pintype "passive"))
      (node (ref "SUPPLY1") (pin "P$2") (pinfunction "P$2_P$2") (pintype "bidirectional"))
    )
    (net (code "4") (name "BAT1") (class "Default")
      (node (ref "BAT1") (pin "BAT") (pinfunction "BAT_BAT") (pintype "bidirectional"))
      (node (ref "BAT1_PWR") (pin "A") (pinfunction "A_A") (pintype "passive"))
      (node (ref "BAT1_TP") (pin "TP") (pinfunction "TP_TP") (pintype "input"))
      (node (ref "Q3") (pin "1") (pinfunction "S_1") (pintype "passive"))
      (node (ref "R27") (pin "2") (pinfunction "2_2") (pintype "passive"))
      (node (ref "R31") (pin "1") (pinfunction "1_1") (pintype "passive"))
    )
    (net (code "5") (name "BAT1_BAL") (class "Default")
      (node (ref "BAT1") (pin "BAL") (pinfunction "BAL_BAL") (pintype "bidirectional"))
      (node (ref "BAT1_BAL") (pin "TP") (pinfunction "TP_TP") (pintype "input"))
      (node (ref "R30") (pin "1") (pinfunction "1_1") (pintype "passive"))
    )
    (net (code "6") (name "BAT1_RET") (class "Default")
      (node (ref "BAT1") (pin "RET") (pinfunction "RET_RET") (pintype "bidirectional"))
      (node (ref "BAT1_RET") (pin "TP") (pinfunction "TP_TP") (pintype "input"))
      (node (ref "R32") (pin "1") (pinfunction "1_1") (pintype "passive"))
      (node (ref "R33") (pin "2") (pinfunction "2_2") (pintype "passive"))
    )
    (net (code "7") (name "BAT1_STAT1") (class "Default")
      (node (ref "R7") (pin "1") (pinfunction "1_1") (pintype "passive"))
      (node (ref "R79") (pin "2") (pinfunction "2_2") (pintype "passive"))
      (node (ref "SYSTEM") (pin "P$1") (pinfunction "1_P$1") (pintype "passive"))
      (node (ref "U1") (pin "3") (pinfunction "STAT1_3") (pintype "bidirectional"))
      (node (ref "U12") (pin "D4") (pinfunction "D4_D4") (pintype "bidirectional"))
    )
    (net (code "8") (name "BAT1_STAT2") (class "Default")
      (node (ref "R8") (pin "1") (pinfunction "1_1") (pintype "passive"))
      (node (ref "R80") (pin "2") (pinfunction "2_2") (pintype "passive"))
      (node (ref "SYSTEM") (pin "P$2") (pinfunction "2_P$2") (pintype "passive"))
      (node (ref "U1") (pin "5") (pinfunction "STAT2_5") (pintype "bidirectional"))
      (node (ref "U12") (pin "D5") (pinfunction "D5_D5") (pintype "bidirectional"))
    )
    (net (code "9") (name "BAT1_TS1") (class "Default")
      (node (ref "BAT1_TS") (pin "P$1") (pinfunction "1_P$1") (pintype "passive"))
      (node (ref "R5") (pin "1") (pinfunction "1_1") (pintype "passive"))
      (node (ref "R6") (pin "2") (pinfunction "2_2") (pintype "passive"))
      (node (ref "U1") (pin "4") (pinfunction "TS_4") (pintype "bidirectional"))
    )
    (net (code "10") (name "BAT1_TS2") (class "Default")
      (node (ref "BAT1_TS") (pin "P$2") (pinfunction "2_P$2") (pintype "passive"))
      (node (ref "U2") (pin "4") (pinfunction "TS1_4") (pintype "bidirectional"))
    )
    (net (code "11") (name "BAT2") (class "Default")
      (node (ref "BAT2") (pin "BAT") (pinfunction "BAT_BAT") (pintype "bidirectional"))
      (node (ref "BAT2_PWR") (pin "A") (pinfunction "A_A") (pintype "passive"))
      (node (ref "BAT2_TP") (pin "TP") (pinfunction "TP_TP") (pintype "input"))
      (node (ref "Q4") (pin "3") (pinfunction "S_3") (pintype "passive"))
      (node (ref "R37") (pin "2") (pinfunction "2_2") (pintype "passive"))
      (node (ref "R41") (pin "1") (pinfunction "1_1") (pintype "passive"))
    )
    (net (code "12") (name "BAT2_BAL") (class "Default")
      (node (ref "BAT2") (pin "BAL") (pinfunction "BAL_BAL") (pintype "bidirectional"))
      (node (ref "BAT2_BAL") (pin "TP") (pinfunction "TP_TP") (pintype "input"))
      (node (ref "R40") (pin "1") (pinfunction "1_1") (pintype "passive"))
    )
    (net (code "13") (name "BAT2_RET") (class "Default")
      (node (ref "BAT2") (pin "RET") (pinfunction "RET_RET") (pintype "bidirectional"))
      (node (ref "BAT2_RET") (pin "TP") (pinfunction "TP_TP") (pintype "input"))
      (node (ref "R42") (pin "1") (pinfunction "1_1") (pintype "passive"))
      (node (ref "R43") (pin "2") (pinfunction "2_2") (pintype "passive"))
    )
    (net (code "14") (name "BAT2_STAT1") (class "Default")
      (node (ref "R20") (pin "1") (pinfunction "1_1") (pintype "passive"))
      (node (ref "R81") (pin "2") (pinfunction "2_2") (pintype "passive"))
      (node (ref "SYSTEM") (pin "P$3") (pinfunction "3_P$3") (pintype "passive"))
      (node (ref "U12") (pin "D7") (pinfunction "D7_D7") (pintype "bidirectional"))
      (node (ref "U4") (pin "3") (pinfunction "STAT1_3") (pintype "bidirectional"))
    )
    (net (code "15") (name "BAT2_STAT2") (class "Default")
      (node (ref "R21") (pin "1") (pinfunction "1_1") (pintype "passive"))
      (node (ref "R82") (pin "2") (pinfunction "2_2") (pintype "passive"))
      (node (ref "SYSTEM") (pin "P$4") (pinfunction "4_P$4") (pintype "passive"))
      (node (ref "U12") (pin "D6") (pinfunction "D6_D6") (pintype "bidirectional"))
      (node (ref "U4") (pin "5") (pinfunction "STAT2_5") (pintype "bidirectional"))
    )
    (net (code "16") (name "BAT2_TS1") (class "Default")
      (node (ref "BAT2_TS") (pin "P$1") (pinfunction "1_P$1") (pintype "passive"))
      (node (ref "R16") (pin "1") (pinfunction "1_1") (pintype "passive"))
      (node (ref "R17") (pin "2") (pinfunction "2_2") (pintype "passive"))
      (node (ref "U4") (pin "4") (pinfunction "TS_4") (pintype "bidirectional"))
    )
    (net (code "17") (name "BAT2_TS2") (class "Default")
      (node (ref "BAT2_TS") (pin "P$2") (pinfunction "2_P$2") (pintype "passive"))
      (node (ref "U3") (pin "4") (pinfunction "TS1_4") (pintype "bidirectional"))
    )
    (net (code "18") (name "BAT_SELECT") (class "Default")
      (node (ref "SYSTEM") (pin "P$7") (pinfunction "7_P$7") (pintype "passive"))
      (node (ref "U10") (pin "1") (pinfunction "OUT_1") (pintype "output"))
      (node (ref "U12") (pin "D0") (pinfunction "D0_D0") (pintype "bidirectional"))
      (node (ref "U8") (pin "2") (pinfunction "I_2") (pintype "input"))
      (node (ref "U9") (pin "2") (pinfunction "I_2") (pintype "input"))
    )
    (net (code "19") (name "COS") (class "Default")
      (node (ref "R76") (pin "1") (pinfunction "1_1") (pintype "passive"))
      (node (ref "U12") (pin "A6") (pinfunction "A6_A6") (pintype "bidirectional"))
      (node (ref "U17") (pin "7") (pinfunction "OUT_7") (pintype "output"))
    )
    (net (code "20") (name "DIM") (class "Default")
      (node (ref "MASTHEAD") (pin "P$3") (pinfunction "3_P$3") (pintype "passive"))
      (node (ref "U12") (pin "D10") (pinfunction "D10/MISO_D10") (pintype "bidirectional"))
    )
    (net (code "21") (name "GND") (class "Default")
      (node (ref "ANEMOMETER") (pin "P$4") (pinfunction "4_P$4") (pintype "passive"))
      (node (ref "BAT1_TS") (pin "P$3") (pinfunction "3_P$3") (pintype "passive"))
      (node (ref "BAT2_TS") (pin "P$3") (pinfunction "3_P$3") (pintype "passive"))
      (node (ref "C1") (pin "2") (pinfunction "2_2") (pintype "passive"))
      (node (ref "C11") (pin "2") (pinfunction "2_2") (pintype "passive"))
      (node (ref "C12") (pin "2") (pinfunction "2_2") (pintype "passive"))
      (node (ref "C13") (pin "2") (pinfunction "2_2") (pintype "passive"))
      (node (ref "C15") (pin "2") (pinfunction "2_2") (pintype "passive"))
      (node (ref "C18") (pin "2") (pinfunction "2_2") (pintype "passive"))
      (node (ref "C19") (pin "2") (pinfunction "2_2") (pintype "passive"))
      (node (ref "C2") (pin "2") (pinfunction "2_2") (pintype "passive"))
      (node (ref "C21") (pin "2") (pinfunction "2_2") (pintype "passive"))
      (node (ref "C23") (pin "2") (pinfunction "2_2") (pintype "passive"))
      (node (ref "C25") (pin "2") (pinfunction "2_2") (pintype "passive"))
      (node (ref "C26") (pin "2") (pinfunction "2_2") (pintype "passive"))
      (node (ref "C29") (pin "2") (pinfunction "2_2") (pintype "passive"))
      (node (ref "C30") (pin "2") (pinfunction "2_2") (pintype "passive"))
      (node (ref "C31") (pin "2") (pinfunction "2_2") (pintype "passive"))
      (node (ref "C32") (pin "2") (pinfunction "2_2") (pintype "passive"))
      (node (ref "C33") (pin "2") (pinfunction "2_2") (pintype "passive"))
      (node (ref "C34") (pin "2") (pinfunction "2_2") (pintype "passive"))
      (node (ref "C35") (pin "2") (pinfunction "2_2") (pintype "passive"))
      (node (ref "C36") (pin "2") (pinfunction "2_2") (pintype "passive"))
      (node (ref "C37") (pin "2") (pinfunction "2_2") (pintype "passive"))
      (node (ref "C38") (pin "2") (pinfunction "2_2") (pintype "passive"))
      (node (ref "C39") (pin "2") (pinfunction "2_2") (pintype "passive"))
      (node (ref "C6") (pin "2") (pinfunction "2_2") (pintype "passive"))
      (node (ref "C7") (pin "2") (pinfunction "2_2") (pintype "passive"))
      (node (ref "C8") (pin "2") (pinfunction "2_2") (pintype "passive"))
      (node (ref "C9") (pin "2") (pinfunction "2_2") (pintype "passive"))
      (node (ref "H1") (pin "B3,2") (pinfunction "MOUNT_B3,2") (pintype "passive"))
      (node (ref "H2") (pin "B3,2") (pinfunction "MOUNT_B3,2") (pintype "passive"))
      (node (ref "H3") (pin "B3,2") (pinfunction "MOUNT_B3,2") (pintype "passive"))
      (node (ref "JP1") (pin "3") (pinfunction "3_3") (pintype "passive"))
      (node (ref "JP2") (pin "1") (pinfunction "1_1") (pintype "passive"))
      (node (ref "MASTHEAD") (pin "P$4") (pinfunction "4_P$4") (pintype "passive"))
      (node (ref "PANEL1_NEG") (pin "TP") (pinfunction "TP_TP") (pintype "input"))
      (node (ref "PANEL2_NEG") (pin "TP") (pinfunction "TP_TP") (pintype "input"))
      (node (ref "PWR_OUT") (pin "N") (pinfunction "N_N") (pintype "bidirectional"))
      (node (ref "Q1") (pin "1") (pinfunction "S_1") (pintype "passive"))
      (node (ref "Q2") (pin "1") (pinfunction "S_1") (pintype "passive"))
      (node (ref "R32") (pin "2") (pinfunction "2_2") (pintype "passive"))
      (node (ref "R34") (pin "2") (pinfunction "2_2") (pintype "passive"))
      (node (ref "R42") (pin "2") (pinfunction "2_2") (pintype "passive"))
      (node (ref "R44") (pin "2") (pinfunction "2_2") (pintype "passive"))
      (node (ref "R55") (pin "2") (pinfunction "2_2") (pintype "passive"))
      (node (ref "R60") (pin "1") (pinfunction "1_1") (pintype "passive"))
      (node (ref "R62") (pin "1") (pinfunction "1_1") (pintype "passive"))
      (node (ref "R64") (pin "1") (pinfunction "1_1") (pintype "passive"))
      (node (ref "R78") (pin "1") (pinfunction "1_1") (pintype "passive"))
      (node (ref "R83") (pin "1") (pinfunction "1_1") (pintype "passive"))
      (node (ref "R84") (pin "1") (pinfunction "1_1") (pintype "passive"))
      (node (ref "R85") (pin "1") (pinfunction "1_1") (pintype "passive"))
      (node (ref "R86") (pin "1") (pinfunction "1_1") (pintype "passive"))
      (node (ref "R87") (pin "1") (pinfunction "1_1") (pintype "passive"))
      (node (ref "R88") (pin "1") (pinfunction "1_1") (pintype "passive"))
      (node (ref "ROTATION") (pin "P$4") (pinfunction "4_P$4") (pintype "passive"))
      (node (ref "SUPPLY1") (pin "P$1") (pinfunction "P$1_P$1") (pintype "bidirectional"))
      (node (ref "SYSTEM") (pin "P$15") (pinfunction "15_P$15") (pintype "passive"))
      (node (ref "TAIL") (pin "P$3") (pinfunction "3_P$3") (pintype "passive"))
      (node (ref "U1") (pin "11") (pinfunction "PGND_11") (pintype "bidirectional"))
      (node (ref "U1") (pin "TH") (pinfunction "THERM_TH") (pintype "bidirectional"))
      (node (ref "U10") (pin "5") (pinfunction "GND_5") (pintype "power_in"))
      (node (ref "U11") (pin "2") (pinfunction "GND_2") (pintype "input"))
      (node (ref "U12") (pin "GND") (pinfunction "GND_GND") (pintype "bidirectional"))
      (node (ref "U13") (pin "2") (pinfunction "GND_2") (pintype "bidirectional"))
      (node (ref "U13") (pin "3") (pinfunction "~{EN}_3") (pintype "bidirectional"))
      (node (ref "U14") (pin "3") (pinfunction "GND_3") (pintype "power_in"))
      (node (ref "U15") (pin "3") (pinfunction "GND_3") (pintype "power_in"))
      (node (ref "U16") (pin "3") (pinfunction "GND_3") (pintype "power_in"))
      (node (ref "U17") (pin "4") (pinfunction "P$V-_4") (pintype "bidirectional"))
      (node (ref "U2") (pin "1") (pinfunction "VSS_1") (pintype "bidirectional"))
      (node (ref "U2") (pin "EP") (pinfunction "THERM_EP") (pintype "bidirectional"))
      (node (ref "U2") (pin "EP1") (pinfunction "THERM_EP1") (pintype "bidirectional"))
      (node (ref "U2") (pin "EP2") (pinfunction "THERM_EP2") (pintype "bidirectional"))
      (node (ref "U2") (pin "EP3") (pinfunction "THERM_EP3") (pintype "bidirectional"))
      (node (ref "U2") (pin "EP4") (pinfunction "THERM_EP4") (pintype "bidirectional"))
      (node (ref "U3") (pin "1") (pinfunction "VSS_1") (pintype "bidirectional"))
      (node (ref "U3") (pin "EP") (pinfunction "THERM_EP") (pintype "bidirectional"))
      (node (ref "U3") (pin "EP1") (pinfunction "THERM_EP1") (pintype "bidirectional"))
      (node (ref "U3") (pin "EP2") (pinfunction "THERM_EP2") (pintype "bidirectional"))
      (node (ref "U3") (pin "EP3") (pinfunction "THERM_EP3") (pintype "bidirectional"))
      (node (ref "U3") (pin "EP4") (pinfunction "THERM_EP4") (pintype "bidirectional"))
      (node (ref "U4") (pin "11") (pinfunction "PGND_11") (pintype "bidirectional"))
      (node (ref "U4") (pin "TH") (pinfunction "THERM_TH") (pintype "bidirectional"))
      (node (ref "U5") (pin "7") (pinfunction "GND_7") (pintype "bidirectional"))
      (node (ref "U6") (pin "2") (pinfunction "GND_2") (pintype "bidirectional"))
      (node (ref "U7") (pin "2") (pinfunction "GND_2") (pintype "bidirectional"))
      (node (ref "U8") (pin "3") (pinfunction "GND_3") (pintype "power_in"))
      (node (ref "U9") (pin "3") (pinfunction "GND_3") (pintype "power_in"))
    )
    (net (code "22") (name "LOGIC_PWR") (class "Default")
      (node (ref "C33") (pin "1") (pinfunction "1_1") (pintype "passive"))
      (node (ref "C34") (pin "1") (pinfunction "1_1") (pintype "passive"))
      (node (ref "C35") (pin "1") (pinfunction "1_1") (pintype "passive"))
      (node (ref "C37") (pin "1") (pinfunction "1_1") (pintype "passive"))
      (node (ref "D9") (pin "C") (pinfunction "C_C") (pintype "passive"))
      (node (ref "U10") (pin "2") (pinfunction "V+_2") (pintype "power_in"))
      (node (ref "U11") (pin "5") (pinfunction "OUT_5") (pintype "passive"))
      (node (ref "U8") (pin "5") (pinfunction "VCC_5") (pintype "power_in"))
      (node (ref "U9") (pin "5") (pinfunction "VCC_5") (pintype "power_in"))
    )
    (net (code "23") (name "MASTHEAD_PWR") (class "Default")
      (node (ref "U12") (pin "A3") (pinfunction "A3_A3") (pintype "bidirectional"))
      (node (ref "U14") (pin "2") (pinfunction "I_2") (pintype "input"))
    )
    (net (code "24") (name "MPPSET1") (class "Default")
      (node (ref "Q6") (pin "3") (pinfunction "D_3") (pintype "bidirectional"))
      (node (ref "R3") (pin "1") (pinfunction "1_1") (pintype "passive"))
      (node (ref "R4") (pin "2") (pinfunction "2_2") (pintype "passive"))
      (node (ref "U1") (pin "2") (pinfunction "MPPSET_2") (pintype "bidirectional"))
    )
    (net (code "25") (name "MPPSET2") (class "Default")
      (node (ref "Q7") (pin "3") (pinfunction "D_3") (pintype "bidirectional"))
      (node (ref "R14") (pin "1") (pinfunction "1_1") (pintype "passive"))
      (node (ref "R15") (pin "2") (pinfunction "2_2") (pintype "passive"))
      (node (ref "U4") (pin "2") (pinfunction "MPPSET_2") (pintype "bidirectional"))
    )
    (net (code "26") (name "NEOPIXEL") (class "Default")
      (node (ref "MASTHEAD") (pin "P$2") (pinfunction "2_P$2") (pintype "passive"))
      (node (ref "U12") (pin "D9") (pinfunction "D9/SCK_D9") (pintype "bidirectional"))
    )
    (net (code "27") (name "Net-(3V3_PWR-PadC)") (class "Default")
      (node (ref "3V3_PWR") (pin "C") (pinfunction "C_C") (pintype "passive"))
      (node (ref "R83") (pin "2") (pinfunction "2_2") (pintype "passive"))
    )
    (net (code "28") (name "Net-(5V_PWR-PadC)") (class "Default")
      (node (ref "5V_PWR") (pin "C") (pinfunction "C_C") (pintype "passive"))
      (node (ref "R84") (pin "2") (pinfunction "2_2") (pintype "passive"))
    )
    (net (code "29") (name "Net-(ANEMOMETER-1)") (class "Default")
      (node (ref "ANEMOMETER") (pin "P$1") (pinfunction "1_P$1") (pintype "passive"))
      (node (ref "Q10") (pin "3") (pinfunction "D_3") (pintype "bidirectional"))
    )
    (net (code "30") (name "Net-(BAT1_PWR-PadC)") (class "Default")
      (node (ref "BAT1_PWR") (pin "C") (pinfunction "C_C") (pintype "passive"))
      (node (ref "R85") (pin "2") (pinfunction "2_2") (pintype "passive"))
    )
    (net (code "31") (name "Net-(BAT1_STAT1-PadC)") (class "Default")
      (node (ref "BAT1_STAT1") (pin "C") (pinfunction "C_C") (pintype "passive"))
      (node (ref "R79") (pin "1") (pinfunction "1_1") (pintype "passive"))
    )
    (net (code "32") (name "Net-(BAT1_STAT2-PadC)") (class "Default")
      (node (ref "BAT1_STAT2") (pin "C") (pinfunction "C_C") (pintype "passive"))
      (node (ref "R80") (pin "1") (pinfunction "1_1") (pintype "passive"))
    )
    (net (code "33") (name "Net-(BAT2_PWR-PadC)") (class "Default")
      (node (ref "BAT2_PWR") (pin "C") (pinfunction "C_C") (pintype "passive"))
      (node (ref "R86") (pin "2") (pinfunction "2_2") (pintype "passive"))
    )
    (net (code "34") (name "Net-(BAT2_STAT1-PadC)") (class "Default")
      (node (ref "BAT2_STAT1") (pin "C") (pinfunction "C_C") (pintype "passive"))
      (node (ref "R81") (pin "1") (pinfunction "1_1") (pintype "passive"))
    )
    (net (code "35") (name "Net-(BAT2_STAT2-PadC)") (class "Default")
      (node (ref "BAT2_STAT2") (pin "C") (pinfunction "C_C") (pintype "passive"))
      (node (ref "R82") (pin "1") (pinfunction "1_1") (pintype "passive"))
    )
    (net (code "36") (name "Net-(C1-Pad1)") (class "Default")
      (node (ref "C1") (pin "1") (pinfunction "1_1") (pintype "passive"))
      (node (ref "R1") (pin "1") (pinfunction "1_1") (pintype "passive"))
    )
    (net (code "37") (name "Net-(C2-Pad1)") (class "Default")
      (node (ref "C2") (pin "1") (pinfunction "1_1") (pintype "passive"))
      (node (ref "C7") (pin "1") (pinfunction "1_1") (pintype "passive"))
      (node (ref "D1") (pin "C") (pinfunction "C_C") (pintype "passive"))
      (node (ref "Q1") (pin "5") (pinfunction "D_5") (pintype "passive"))
      (node (ref "Q1") (pin "6") (pinfunction "D_6") (pintype "passive"))
      (node (ref "R2") (pin "1") (pinfunction "1_1") (pintype "passive"))
      (node (ref "R3") (pin "2") (pinfunction "2_2") (pintype "passive"))
    )
    (net (code "38") (name "Net-(C11-Pad1)") (class "Default")
      (node (ref "C11") (pin "1") (pinfunction "1_1") (pintype "passive"))
      (node (ref "R13") (pin "1") (pinfunction "1_1") (pintype "passive"))
    )
    (net (code "39") (name "Net-(C12-Pad1)") (class "Default")
      (node (ref "C12") (pin "1") (pinfunction "1_1") (pintype "passive"))
      (node (ref "C13") (pin "1") (pinfunction "1_1") (pintype "passive"))
      (node (ref "D2") (pin "C") (pinfunction "C_C") (pintype "passive"))
      (node (ref "Q2") (pin "5") (pinfunction "D_5") (pintype "passive"))
      (node (ref "Q2") (pin "6") (pinfunction "D_6") (pintype "passive"))
      (node (ref "R14") (pin "2") (pinfunction "2_2") (pintype "passive"))
      (node (ref "R18") (pin "1") (pinfunction "1_1") (pintype "passive"))
    )
    (net (code "40") (name "Net-(D3-A)") (class "Default")
      (node (ref "C6") (pin "1") (pinfunction "1_1") (pintype "passive"))
      (node (ref "D3") (pin "1") (pinfunction "A_1") (pintype "passive"))
      (node (ref "U1") (pin "12") (pinfunction "REGN_12") (pintype "bidirectional"))
    )
    (net (code "41") (name "Net-(D3-C)") (class "Default")
      (node (ref "C4") (pin "1") (pinfunction "1_1") (pintype "passive"))
      (node (ref "D3") (pin "3") (pinfunction "C_3") (pintype "passive"))
      (node (ref "U1") (pin "16") (pinfunction "BTST_16") (pintype "bidirectional"))
    )
    (net (code "42") (name "Net-(D4-A)") (class "Default")
      (node (ref "C15") (pin "1") (pinfunction "1_1") (pintype "passive"))
      (node (ref "D4") (pin "1") (pinfunction "A_1") (pintype "passive"))
      (node (ref "U4") (pin "12") (pinfunction "REGN_12") (pintype "bidirectional"))
    )
    (net (code "43") (name "Net-(D4-C)") (class "Default")
      (node (ref "C16") (pin "1") (pinfunction "1_1") (pintype "passive"))
      (node (ref "D4") (pin "3") (pinfunction "C_3") (pintype "passive"))
      (node (ref "U4") (pin "16") (pinfunction "BTST_16") (pintype "bidirectional"))
    )
    (net (code "44") (name "Net-(MASTHEAD-1)") (class "Default")
      (node (ref "MASTHEAD") (pin "P$1") (pinfunction "1_P$1") (pintype "passive"))
      (node (ref "Q9") (pin "3") (pinfunction "D_3") (pintype "bidirectional"))
    )
    (net (code "45") (name "Net-(PANEL1_PWR-PadC)") (class "Default")
      (node (ref "PANEL1_PWR") (pin "C") (pinfunction "C_C") (pintype "passive"))
      (node (ref "R87") (pin "2") (pinfunction "2_2") (pintype "passive"))
    )
    (net (code "46") (name "Net-(PANEL2_PWR-PadC)") (class "Default")
      (node (ref "PANEL2_PWR") (pin "C") (pinfunction "C_C") (pintype "passive"))
      (node (ref "R88") (pin "2") (pinfunction "2_2") (pintype "passive"))
    )
    (net (code "47") (name "Net-(Q1A-G)") (class "Default")
      (node (ref "Q1") (pin "4") (pinfunction "G_4") (pintype "passive"))
      (node (ref "U1") (pin "15") (pinfunction "HIDRV_15") (pintype "bidirectional"))
    )
    (net (code "48") (name "Net-(Q1A-S)") (class "Default")
      (node (ref "C4") (pin "2") (pinfunction "2_2") (pintype "passive"))
      (node (ref "L1") (pin "1") (pinfunction "1_1") (pintype "passive"))
      (node (ref "Q1") (pin "3") (pinfunction "S_3") (pintype "passive"))
      (node (ref "Q1") (pin "7") (pinfunction "D_7") (pintype "passive"))
      (node (ref "Q1") (pin "8") (pinfunction "D_8") (pintype "passive"))
      (node (ref "U1") (pin "14") (pinfunction "PH_14") (pintype "bidirectional"))
    )
    (net (code "49") (name "Net-(Q1B-G)") (class "Default")
      (node (ref "Q1") (pin "2") (pinfunction "G_2") (pintype "passive"))
      (node (ref "U1") (pin "13") (pinfunction "LODRV_13") (pintype "bidirectional"))
    )
    (net (code "50") (name "Net-(Q2A-G)") (class "Default")
      (node (ref "Q2") (pin "4") (pinfunction "G_4") (pintype "passive"))
      (node (ref "U4") (pin "15") (pinfunction "HIDRV_15") (pintype "bidirectional"))
    )
    (net (code "51") (name "Net-(Q2A-S)") (class "Default")
      (node (ref "C16") (pin "2") (pinfunction "2_2") (pintype "passive"))
      (node (ref "L2") (pin "2") (pinfunction "2_2") (pintype "passive"))
      (node (ref "Q2") (pin "3") (pinfunction "S_3") (pintype "passive"))
      (node (ref "Q2") (pin "7") (pinfunction "D_7") (pintype "passive"))
      (node (ref "Q2") (pin "8") (pinfunction "D_8") (pintype "passive"))
      (node (ref "U4") (pin "14") (pinfunction "PH_14") (pintype "bidirectional"))
    )
    (net (code "52") (name "Net-(Q2B-G)") (class "Default")
      (node (ref "Q2") (pin "2") (pinfunction "G_2") (pintype "passive"))
      (node (ref "U4") (pin "13") (pinfunction "LODRV_13") (pintype "bidirectional"))
    )
    (net (code "53") (name "Net-(Q3A-D-Pad5)") (class "Default")
      (node (ref "Q3") (pin "5") (pinfunction "D_5") (pintype "passive"))
      (node (ref "Q3") (pin "6") (pinfunction "D_6") (pintype "passive"))
      (node (ref "Q3") (pin "7") (pinfunction "D_7") (pintype "passive"))
      (node (ref "Q3") (pin "8") (pinfunction "D_8") (pintype "passive"))
    )
    (net (code "54") (name "Net-(Q3A-G)") (class "Default")
      (node (ref "Q3") (pin "4") (pinfunction "G_4") (pintype "passive"))
      (node (ref "R25") (pin "2") (pinfunction "2_2") (pintype "passive"))
      (node (ref "R28") (pin "1") (pinfunction "1_1") (pintype "passive"))
    )
    (net (code "55") (name "Net-(Q3B-G)") (class "Default")
      (node (ref "Q3") (pin "2") (pinfunction "G_2") (pintype "passive"))
      (node (ref "R26") (pin "2") (pinfunction "2_2") (pintype "passive"))
      (node (ref "R27") (pin "1") (pinfunction "1_1") (pintype "passive"))
    )
    (net (code "56") (name "Net-(Q4A-D-Pad5)") (class "Default")
      (node (ref "Q4") (pin "5") (pinfunction "D_5") (pintype "passive"))
      (node (ref "Q4") (pin "6") (pinfunction "D_6") (pintype "passive"))
      (node (ref "Q4") (pin "7") (pinfunction "D_7") (pintype "passive"))
      (node (ref "Q4") (pin "8") (pinfunction "D_8") (pintype "passive"))
    )
    (net (code "57") (name "Net-(Q4A-G)") (class "Default")
      (node (ref "Q4") (pin "4") (pinfunction "G_4") (pintype "passive"))
      (node (ref "R37") (pin "1") (pinfunction "1_1") (pintype "passive"))
      (node (ref "R39") (pin "2") (pinfunction "2_2") (pintype "passive"))
    )
    (net (code "58") (name "Net-(Q4B-G)") (class "Default")
      (node (ref "Q4") (pin "2") (pinfunction "G_2") (pintype "passive"))
      (node (ref "R35") (pin "1") (pinfunction "1_1") (pintype "passive"))
      (node (ref "R38") (pin "2") (pinfunction "2_2") (pintype "passive"))
    )
    (net (code "59") (name "Net-(Q5A-G)") (class "Default")
      (node (ref "Q5") (pin "2") (pinfunction "G_2") (pintype "passive"))
      (node (ref "R52") (pin "2") (pinfunction "2_2") (pintype "passive"))
      (node (ref "R54") (pin "1") (pinfunction "1_1") (pintype "passive"))
    )
    (net (code "60") (name "Net-(Q5B-G)") (class "Default")
      (node (ref "Q5") (pin "4") (pinfunction "G_4") (pintype "passive"))
      (node (ref "R51") (pin "2") (pinfunction "2_2") (pintype "passive"))
      (node (ref "R53") (pin "1") (pinfunction "1_1") (pintype "passive"))
    )
    (net (code "61") (name "Net-(Q6-G)") (class "Default")
      (node (ref "Q6") (pin "1") (pinfunction "G_1") (pintype "bidirectional"))
      (node (ref "R12") (pin "2") (pinfunction "2_2") (pintype "passive"))
      (node (ref "R56") (pin "2") (pinfunction "2_2") (pintype "passive"))
    )
    (net (code "62") (name "Net-(Q7-G)") (class "Default")
      (node (ref "Q7") (pin "1") (pinfunction "G_1") (pintype "bidirectional"))
      (node (ref "R19") (pin "2") (pinfunction "2_2") (pintype "passive"))
      (node (ref "R57") (pin "2") (pinfunction "2_2") (pintype "passive"))
    )
    (net (code "63") (name "Net-(Q8-D)") (class "Default")
      (node (ref "Q8") (pin "3") (pinfunction "D_3") (pintype "bidirectional"))
      (node (ref "ROTATION") (pin "P$1") (pinfunction "1_P$1") (pintype "passive"))
    )
    (net (code "64") (name "Net-(Q8-G)") (class "Default")
      (node (ref "Q8") (pin "1") (pinfunction "G_1") (pintype "bidirectional"))
      (node (ref "R68") (pin "1") (pinfunction "1_1") (pintype "passive"))
    )
    (net (code "65") (name "Net-(Q9-G)") (class "Default")
      (node (ref "Q9") (pin "1") (pinfunction "G_1") (pintype "bidirectional"))
      (node (ref "R65") (pin "1") (pinfunction "1_1") (pintype "passive"))
    )
    (net (code "66") (name "Net-(Q10-G)") (class "Default")
      (node (ref "Q10") (pin "1") (pinfunction "G_1") (pintype "bidirectional"))
      (node (ref "R69") (pin "1") (pinfunction "1_1") (pintype "passive"))
    )
    (net (code "67") (name "Net-(Q11-D)") (class "Default")
      (node (ref "Q11") (pin "3") (pinfunction "D_3") (pintype "bidirectional"))
      (node (ref "TAIL") (pin "P$1") (pinfunction "1_P$1") (pintype "passive"))
    )
    (net (code "68") (name "Net-(Q11-G)") (class "Default")
      (node (ref "Q11") (pin "1") (pinfunction "G_1") (pintype "bidirectional"))
      (node (ref "R71") (pin "1") (pinfunction "1_1") (pintype "passive"))
    )
    (net (code "69") (name "Net-(ROTATION-2)") (class "Default")
      (node (ref "R73") (pin "2") (pinfunction "2_2") (pintype "passive"))
      (node (ref "ROTATION") (pin "P$2") (pinfunction "2_P$2") (pintype "passive"))
    )
    (net (code "70") (name "Net-(ROTATION-3)") (class "Default")
      (node (ref "R75") (pin "2") (pinfunction "2_2") (pintype "passive"))
      (node (ref "ROTATION") (pin "P$3") (pinfunction "3_P$3") (pintype "passive"))
    )
    (net (code "71") (name "Net-(U1-SRP)") (class "Default")
      (node (ref "C3") (pin "1") (pinfunction "1_1") (pintype "passive"))
      (node (ref "L1") (pin "2") (pinfunction "2_2") (pintype "passive"))
      (node (ref "R9") (pin "1") (pinfunction "1_1") (pintype "passive"))
      (node (ref "U1") (pin "10") (pinfunction "SRP_10") (pintype "bidirectional"))
    )
    (net (code "72") (name "Net-(U1-VCC)") (class "Default")
      (node (ref "R2") (pin "2") (pinfunction "2_2") (pintype "passive"))
      (node (ref "U1") (pin "1") (pinfunction "VCC_1") (pintype "bidirectional"))
    )
    (net (code "73") (name "Net-(U1-VFB)") (class "Default")
      (node (ref "C10") (pin "2") (pinfunction "2_2") (pintype "passive"))
      (node (ref "R10") (pin "1") (pinfunction "1_1") (pintype "passive"))
      (node (ref "R11") (pin "2") (pinfunction "2_2") (pintype "passive"))
      (node (ref "U1") (pin "8") (pinfunction "VFB_8") (pintype "bidirectional"))
    )
    (net (code "74") (name "Net-(U2-CHG)") (class "Default")
      (node (ref "R26") (pin "1") (pinfunction "1_1") (pintype "passive"))
      (node (ref "U2") (pin "9") (pinfunction "CHG_9") (pintype "bidirectional"))
    )
    (net (code "75") (name "Net-(U2-DSG)") (class "Default")
      (node (ref "R25") (pin "1") (pinfunction "1_1") (pintype "passive"))
      (node (ref "U2") (pin "7") (pinfunction "DSG_7") (pintype "bidirectional"))
    )
    (net (code "76") (name "Net-(U2-PACK)") (class "Default")
      (node (ref "R29") (pin "1") (pinfunction "1_1") (pintype "passive"))
      (node (ref "U2") (pin "8") (pinfunction "PACK_8") (pintype "bidirectional"))
    )
    (net (code "77") (name "Net-(U2-PBI)") (class "Default")
      (node (ref "C23") (pin "1") (pinfunction "1_1") (pintype "passive"))
      (node (ref "U2") (pin "10") (pinfunction "PBI_10") (pintype "bidirectional"))
    )
    (net (code "78") (name "Net-(U2-SRN)") (class "Default")
      (node (ref "C24") (pin "1") (pinfunction "1_1") (pintype "passive"))
      (node (ref "R33") (pin "1") (pinfunction "1_1") (pintype "passive"))
      (node (ref "U2") (pin "2") (pinfunction "SRN_2") (pintype "bidirectional"))
    )
    (net (code "79") (name "Net-(U2-SRP)") (class "Default")
      (node (ref "C24") (pin "2") (pinfunction "2_2") (pintype "passive"))
      (node (ref "R34") (pin "1") (pinfunction "1_1") (pintype "passive"))
      (node (ref "U2") (pin "3") (pinfunction "SRP_3") (pintype "bidirectional"))
    )
    (net (code "80") (name "Net-(U2-VC1)") (class "Default")
      (node (ref "C21") (pin "1") (pinfunction "1_1") (pintype "passive"))
      (node (ref "C22") (pin "1") (pinfunction "1_1") (pintype "passive"))
      (node (ref "R30") (pin "2") (pinfunction "2_2") (pintype "passive"))
      (node (ref "U2") (pin "12") (pinfunction "VC1_12") (pintype "bidirectional"))
    )
    (net (code "81") (name "Net-(U2-VC2)") (class "Default")
      (node (ref "C22") (pin "2") (pinfunction "2_2") (pintype "passive"))
      (node (ref "R31") (pin "2") (pinfunction "2_2") (pintype "passive"))
      (node (ref "U2") (pin "11") (pinfunction "VC2_11") (pintype "bidirectional"))
    )
    (net (code "82") (name "Net-(U3-CHG)") (class "Default")
      (node (ref "R39") (pin "1") (pinfunction "1_1") (pintype "passive"))
      (node (ref "U3") (pin "9") (pinfunction "CHG_9") (pintype "bidirectional"))
    )
    (net (code "83") (name "Net-(U3-DSG)") (class "Default")
      (node (ref "R38") (pin "1") (pinfunction "1_1") (pintype "passive"))
      (node (ref "U3") (pin "7") (pinfunction "DSG_7") (pintype "bidirectional"))
    )
    (net (code "84") (name "Net-(U3-PACK)") (class "Default")
      (node (ref "R36") (pin "1") (pinfunction "1_1") (pintype "passive"))
      (node (ref "U3") (pin "8") (pinfunction "PACK_8") (pintype "bidirectional"))
    )
    (net (code "85") (name "Net-(U3-PBI)") (class "Default")
      (node (ref "C25") (pin "1") (pinfunction "1_1") (pintype "passive"))
      (node (ref "U3") (pin "10") (pinfunction "PBI_10") (pintype "bidirectional"))
    )
    (net (code "86") (name "Net-(U3-SRN)") (class "Default")
      (node (ref "C28") (pin "1") (pinfunction "1_1") (pintype "passive"))
      (node (ref "R43") (pin "1") (pinfunction "1_1") (pintype "passive"))
      (node (ref "U3") (pin "2") (pinfunction "SRN_2") (pintype "bidirectional"))
    )
    (net (code "87") (name "Net-(U3-SRP)") (class "Default")
      (node (ref "C28") (pin "2") (pinfunction "2_2") (pintype "passive"))
      (node (ref "R44") (pin "1") (pinfunction "1_1") (pintype "passive"))
      (node (ref "U3") (pin "3") (pinfunction "SRP_3") (pintype "bidirectional"))
    )
    (net (code "88") (name "Net-(U3-VC1)") (class "Default")
      (node (ref "C26") (pin "1") (pinfunction "1_1") (pintype "passive"))
      (node (ref "C27") (pin "1") (pinfunction "1_1") (pintype "passive"))
      (node (ref "R40") (pin "2") (pinfunction "2_2") (pintype "passive"))
      (node (ref "U3") (pin "12") (pinfunction "VC1_12") (pintype "bidirectional"))
    )
    (net (code "89") (name "Net-(U3-VC2)") (class "Default")
      (node (ref "C27") (pin "2") (pinfunction "2_2") (pintype "passive"))
      (node (ref "R41") (pin "2") (pinfunction "2_2") (pintype "passive"))
      (node (ref "U3") (pin "11") (pinfunction "VC2_11") (pintype "bidirectional"))
    )
    (net (code "90") (name "Net-(U4-SRP)") (class "Default")
      (node (ref "C17") (pin "1") (pinfunction "1_1") (pintype "passive"))
      (node (ref "L2") (pin "1") (pinfunction "1_1") (pintype "passive"))
      (node (ref "R22") (pin "1") (pinfunction "1_1") (pintype "passive"))
      (node (ref "U4") (pin "10") (pinfunction "SRP_10") (pintype "bidirectional"))
    )
    (net (code "91") (name "Net-(U4-VCC)") (class "Default")
      (node (ref "R18") (pin "2") (pinfunction "2_2") (pintype "passive"))
      (node (ref "U4") (pin "1") (pinfunction "VCC_1") (pintype "bidirectional"))
    )
    (net (code "92") (name "Net-(U4-VFB)") (class "Default")
      (node (ref "C20") (pin "2") (pinfunction "2_2") (pintype "passive"))
      (node (ref "R23") (pin "1") (pinfunction "1_1") (pintype "passive"))
      (node (ref "R24") (pin "2") (pinfunction "2_2") (pintype "passive"))
      (node (ref "U4") (pin "8") (pinfunction "VFB_8") (pintype "bidirectional"))
    )
    (net (code "93") (name "Net-(U5-A0)") (class "Default")
      (node (ref "JP1") (pin "2") (pinfunction "2_2") (pintype "passive"))
      (node (ref "U5") (pin "1") (pinfunction "A0_1") (pintype "bidirectional"))
    )
    (net (code "94") (name "Net-(U5-A1)") (class "Default")
      (node (ref "JP2") (pin "2") (pinfunction "2_2") (pintype "passive"))
      (node (ref "U5") (pin "2") (pinfunction "A1_2") (pintype "bidirectional"))
    )
    (net (code "95") (name "Net-(U8A-O)") (class "Default")
      (node (ref "R53") (pin "2") (pinfunction "2_2") (pintype "passive"))
      (node (ref "U8") (pin "4") (pinfunction "O_4") (pintype "open_collector"))
    )
    (net (code "96") (name "Net-(U9A-O)") (class "Default")
      (node (ref "R54") (pin "2") (pinfunction "2_2") (pintype "passive"))
      (node (ref "U9") (pin "4") (pinfunction "O_4") (pintype "open_collector"))
    )
    (net (code "97") (name "Net-(U11-BP)") (class "Default")
      (node (ref "C36") (pin "1") (pinfunction "1_1") (pintype "passive"))
      (node (ref "U11") (pin "4") (pinfunction "BP_4") (pintype "input"))
    )
    (net (code "98") (name "Net-(U11-IN)") (class "Default")
      (node (ref "D7") (pin "C") (pinfunction "C_C") (pintype "passive"))
      (node (ref "D8") (pin "C") (pinfunction "C_C") (pintype "passive"))
      (node (ref "U11") (pin "1") (pinfunction "IN_1") (pintype "input"))
    )
    (net (code "99") (name "Net-(U12-A0{slash}DAC0)") (class "Default")
      (node (ref "R59") (pin "1") (pinfunction "1_1") (pintype "passive"))
      (node (ref "R60") (pin "2") (pinfunction "2_2") (pintype "passive"))
      (node (ref "U12") (pin "A0") (pinfunction "A0/DAC0_A0") (pintype "bidirectional"))
    )
    (net (code "100") (name "Net-(U12-D14{slash}TX)") (class "Default")
      (node (ref "U12") (pin "D14") (pinfunction "D14/TX_D14") (pintype "bidirectional"))
      (node (ref "U13") (pin "4") (pinfunction "WDI_4") (pintype "bidirectional"))
    )
    (net (code "101") (name "Net-(U12-RESET)") (class "Default")
      (node (ref "U12") (pin "RST") (pinfunction "RESET_RST") (pintype "bidirectional"))
      (node (ref "WDT-RST") (pin "1") (pinfunction "1_1") (pintype "passive"))
    )
    (net (code "102") (name "Net-(U13-~{WDO})") (class "Default")
      (node (ref "U13") (pin "1") (pinfunction "~{WDO}_1") (pintype "bidirectional"))
      (node (ref "WDT-RST") (pin "2") (pinfunction "2_2") (pintype "passive"))
    )
    (net (code "103") (name "Net-(U14A-O)") (class "Default")
      (node (ref "R65") (pin "2") (pinfunction "2_2") (pintype "passive"))
      (node (ref "R66") (pin "2") (pinfunction "2_2") (pintype "passive"))
      (node (ref "U14") (pin "4") (pinfunction "O_4") (pintype "open_collector"))
    )
    (net (code "104") (name "Net-(U15A-O)") (class "Default")
      (node (ref "R71") (pin "2") (pinfunction "2_2") (pintype "passive"))
      (node (ref "R72") (pin "2") (pinfunction "2_2") (pintype "passive"))
      (node (ref "U15") (pin "4") (pinfunction "O_4") (pintype "open_collector"))
    )
    (net (code "105") (name "Net-(U16A-O)") (class "Default")
      (node (ref "R67") (pin "2") (pinfunction "2_2") (pintype "passive"))
      (node (ref "R68") (pin "2") (pinfunction "2_2") (pintype "passive"))
      (node (ref "R69") (pin "2") (pinfunction "2_2") (pintype "passive"))
      (node (ref "R70") (pin "2") (pinfunction "2_2") (pintype "passive"))
      (node (ref "U16") (pin "4") (pinfunction "O_4") (pintype "open_collector"))
    )
    (net (code "106") (name "Net-(U17A-+IN)") (class "Default")
      (node (ref "R77") (pin "1") (pinfunction "1_1") (pintype "passive"))
      (node (ref "R78") (pin "2") (pinfunction "2_2") (pintype "passive"))
      (node (ref "U17") (pin "3") (pinfunction "+IN_3") (pintype "input"))
      (node (ref "U17") (pin "5") (pinfunction "+IN_5") (pintype "input"))
    )
    (net (code "107") (name "Net-(U17A--IN)") (class "Default")
      (node (ref "R73") (pin "1") (pinfunction "1_1") (pintype "passive"))
      (node (ref "R74") (pin "2") (pinfunction "2_2") (pintype "passive"))
      (node (ref "U17") (pin "2") (pinfunction "-IN_2") (pintype "input"))
    )
    (net (code "108") (name "Net-(U17B--IN)") (class "Default")
      (node (ref "R75") (pin "1") (pinfunction "1_1") (pintype "passive"))
      (node (ref "R76") (pin "2") (pinfunction "2_2") (pintype "passive"))
      (node (ref "U17") (pin "6") (pinfunction "-IN_6") (pintype "input"))
    )
    (net (code "109") (name "PANEL1") (class "Default")
      (node (ref "D1") (pin "A") (pinfunction "A_A") (pintype "passive"))
      (node (ref "PANEL1_POS") (pin "TP") (pinfunction "TP_TP") (pintype "input"))
      (node (ref "PANEL1_PWR") (pin "A") (pinfunction "A_A") (pintype "passive"))
      (node (ref "R1") (pin "2") (pinfunction "2_2") (pintype "passive"))
      (node (ref "R61") (pin "2") (pinfunction "2_2") (pintype "passive"))
    )
    (net (code "110") (name "PANEL1_DIV") (class "Default")
      (node (ref "R61") (pin "1") (pinfunction "1_1") (pintype "passive"))
      (node (ref "R62") (pin "2") (pinfunction "2_2") (pintype "passive"))
      (node (ref "SYSTEM") (pin "P$13") (pinfunction "13_P$13") (pintype "passive"))
      (node (ref "U12") (pin "A1") (pinfunction "A1_A1") (pintype "bidirectional"))
    )
    (net (code "111") (name "PANEL2") (class "Default")
      (node (ref "D2") (pin "A") (pinfunction "A_A") (pintype "passive"))
      (node (ref "PANEL2_POS") (pin "TP") (pinfunction "TP_TP") (pintype "input"))
      (node (ref "PANEL2_PWR") (pin "A") (pinfunction "A_A") (pintype "passive"))
      (node (ref "R13") (pin "2") (pinfunction "2_2") (pintype "passive"))
      (node (ref "R63") (pin "2") (pinfunction "2_2") (pintype "passive"))
    )
    (net (code "112") (name "PANEL2_DIV") (class "Default")
      (node (ref "R63") (pin "1") (pinfunction "1_1") (pintype "passive"))
      (node (ref "R64") (pin "2") (pinfunction "2_2") (pintype "passive"))
      (node (ref "SYSTEM") (pin "P$14") (pinfunction "14_P$14") (pintype "passive"))
      (node (ref "U12") (pin "A2") (pinfunction "A2_A2") (pintype "bidirectional"))
    )
    (net (code "113") (name "SCL") (class "Default")
      (node (ref "ANEMOMETER") (pin "P$3") (pinfunction "3_P$3") (pintype "passive"))
      (node (ref "R50") (pin "2") (pinfunction "2_2") (pintype "passive"))
      (node (ref "SYSTEM") (pin "P$9") (pinfunction "9_P$9") (pintype "passive"))
      (node (ref "U12") (pin "D12") (pinfunction "D12/SCL_D12") (pintype "bidirectional"))
      (node (ref "U5") (pin "12") (pinfunction "SCL_12") (pintype "bidirectional"))
    )
    (net (code "114") (name "SCL1") (class "Default")
      (node (ref "R46") (pin "2") (pinfunction "2_2") (pintype "passive"))
      (node (ref "U2") (pin "5") (pinfunction "SCL_5") (pintype "bidirectional"))
      (node (ref "U5") (pin "6") (pinfunction "SC0_6") (pintype "bidirectional"))
    )
    (net (code "115") (name "SCL2") (class "Default")
      (node (ref "R49") (pin "2") (pinfunction "2_2") (pintype "passive"))
      (node (ref "U3") (pin "5") (pinfunction "SCL_5") (pintype "bidirectional"))
      (node (ref "U5") (pin "10") (pinfunction "SC1_10") (pintype "bidirectional"))
    )
    (net (code "116") (name "SDA") (class "Default")
      (node (ref "ANEMOMETER") (pin "P$2") (pinfunction "2_P$2") (pintype "passive"))
      (node (ref "R47") (pin "2") (pinfunction "2_2") (pintype "passive"))
      (node (ref "SYSTEM") (pin "P$8") (pinfunction "8_P$8") (pintype "passive"))
      (node (ref "U12") (pin "D11") (pinfunction "D11/SDA_D11") (pintype "bidirectional"))
      (node (ref "U5") (pin "13") (pinfunction "SDA_13") (pintype "bidirectional"))
    )
    (net (code "117") (name "SDA1") (class "Default")
      (node (ref "R45") (pin "2") (pinfunction "2_2") (pintype "passive"))
      (node (ref "U2") (pin "6") (pinfunction "SDA_6") (pintype "bidirectional"))
      (node (ref "U5") (pin "5") (pinfunction "SD0_5") (pintype "bidirectional"))
    )
    (net (code "118") (name "SDA2") (class "Default")
      (node (ref "R48") (pin "2") (pinfunction "2_2") (pintype "passive"))
      (node (ref "U3") (pin "6") (pinfunction "SDA_6") (pintype "bidirectional"))
      (node (ref "U5") (pin "9") (pinfunction "SD1_9") (pintype "bidirectional"))
    )
    (net (code "119") (name "SENSOR_PWR") (class "Default")
      (node (ref "U12") (pin "D8") (pinfunction "D8/MOSI_D8") (pintype "bidirectional"))
      (node (ref "U16") (pin "2") (pinfunction "I_2") (pintype "input"))
    )
    (net (code "120") (name "SERVO_PWR") (class "Default")
      (node (ref "U12") (pin "D13") (pinfunction "D13/RX_D13") (pintype "bidirectional"))
      (node (ref "U15") (pin "2") (pinfunction "I_2") (pintype "input"))
    )
    (net (code "121") (name "SIN") (class "Default")
      (node (ref "R74") (pin "1") (pinfunction "1_1") (pintype "passive"))
      (node (ref "U12") (pin "A5") (pinfunction "A5_A5") (pintype "bidirectional"))
      (node (ref "U17") (pin "1") (pinfunction "OUT_1") (pintype "output"))
    )
    (net (code "122") (name "TAIL_SERVO") (class "Default")
      (node (ref "TAIL") (pin "P$2") (pinfunction "2_P$2") (pintype "passive"))
      (node (ref "U12") (pin "A4") (pinfunction "A4_A4") (pintype "bidirectional"))
    )
    (net (code "123") (name "VBAT1") (class "Default")
      (node (ref "C10") (pin "1") (pinfunction "1_1") (pintype "passive"))
      (node (ref "C3") (pin "2") (pinfunction "2_2") (pintype "passive"))
      (node (ref "C8") (pin "1") (pinfunction "1_1") (pintype "passive"))
      (node (ref "C9") (pin "1") (pinfunction "1_1") (pintype "passive"))
      (node (ref "D7") (pin "A") (pinfunction "A_A") (pintype "passive"))
      (node (ref "Q3") (pin "3") (pinfunction "S_3") (pintype "passive"))
      (node (ref "Q5") (pin "3") (pinfunction "S_3") (pintype "passive"))
      (node (ref "R10") (pin "2") (pinfunction "2_2") (pintype "passive"))
      (node (ref "R28") (pin "2") (pinfunction "2_2") (pintype "passive"))
      (node (ref "R29") (pin "2") (pinfunction "2_2") (pintype "passive"))
      (node (ref "R51") (pin "1") (pinfunction "1_1") (pintype "passive"))
      (node (ref "R9") (pin "2") (pinfunction "2_2") (pintype "passive"))
      (node (ref "U1") (pin "9") (pinfunction "SRN_9") (pintype "bidirectional"))
      (node (ref "U10") (pin "4") (pinfunction "-IN_4") (pintype "input"))
    )
    (net (code "124") (name "VBAT2") (class "Default")
      (node (ref "C17") (pin "2") (pinfunction "2_2") (pintype "passive"))
      (node (ref "C18") (pin "1") (pinfunction "1_1") (pintype "passive"))
      (node (ref "C19") (pin "1") (pinfunction "1_1") (pintype "passive"))
      (node (ref "C20") (pin "1") (pinfunction "1_1") (pintype "passive"))
      (node (ref "D8") (pin "A") (pinfunction "A_A") (pintype "passive"))
      (node (ref "Q4") (pin "1") (pinfunction "S_1") (pintype "passive"))
      (node (ref "Q5") (pin "1") (pinfunction "S_1") (pintype "passive"))
      (node (ref "R22") (pin "2") (pinfunction "2_2") (pintype "passive"))
      (node (ref "R23") (pin "2") (pinfunction "2_2") (pintype "passive"))
      (node (ref "R35") (pin "2") (pinfunction "2_2") (pintype "passive"))
      (node (ref "R36") (pin "2") (pinfunction "2_2") (pintype "passive"))
      (node (ref "R52") (pin "1") (pinfunction "1_1") (pintype "passive"))
      (node (ref "U10") (pin "3") (pinfunction "+IN_3") (pintype "input"))
      (node (ref "U4") (pin "9") (pinfunction "SRN_9") (pintype "bidirectional"))
    )
    (net (code "125") (name "VREF1") (class "Default")
      (node (ref "C5") (pin "1") (pinfunction "1_1") (pintype "passive"))
      (node (ref "R5") (pin "2") (pinfunction "2_2") (pintype "passive"))
      (node (ref "U1") (pin "6") (pinfunction "VREF_6") (pintype "bidirectional"))
      (node (ref "U1") (pin "7") (pinfunction "TERM_EN_7") (pintype "bidirectional"))
    )
    (net (code "126") (name "VREF2") (class "Default")
      (node (ref "C14") (pin "1") (pinfunction "1_1") (pintype "passive"))
      (node (ref "R16") (pin "2") (pinfunction "2_2") (pintype "passive"))
      (node (ref "U4") (pin "6") (pinfunction "VREF_6") (pintype "bidirectional"))
      (node (ref "U4") (pin "7") (pinfunction "TERM_EN_7") (pintype "bidirectional"))
    )
    (net (code "127") (name "VSELECT") (class "Default")
      (node (ref "PWR_OUT") (pin "P") (pinfunction "P_P") (pintype "bidirectional"))
      (node (ref "Q10") (pin "2") (pinfunction "S_2") (pintype "bidirectional"))
      (node (ref "Q5") (pin "5") (pinfunction "D_5") (pintype "passive"))
      (node (ref "Q5") (pin "6") (pinfunction "D_6") (pintype "passive"))
      (node (ref "Q5") (pin "7") (pinfunction "D_7") (pintype "passive"))
      (node (ref "Q5") (pin "8") (pinfunction "D_8") (pintype "passive"))
      (node (ref "Q9") (pin "2") (pinfunction "S_2") (pintype "bidirectional"))
      (node (ref "R59") (pin "2") (pinfunction "2_2") (pintype "passive"))
      (node (ref "R66") (pin "1") (pinfunction "1_1") (pintype "passive"))
      (node (ref "R70") (pin "1") (pinfunction "1_1") (pintype "passive"))
      (node (ref "U6") (pin "1") (pinfunction "VIN_1") (pintype "bidirectional"))
      (node (ref "U7") (pin "1") (pinfunction "VIN_1") (pintype "bidirectional"))
    )
    (net (code "128") (name "unconnected-(U5-~{INT0}-Pad4)") (class "Default")
      (node (ref "U5") (pin "4") (pinfunction "~{INT0}_4") (pintype "bidirectional"))
    )
    (net (code "129") (name "unconnected-(U5-~{INT1}-Pad8)") (class "Default")
      (node (ref "U5") (pin "8") (pinfunction "~{INT1}_8") (pintype "bidirectional"))
    )
    (net (code "130") (name "unconnected-(U5-~{INT}-Pad11)") (class "Default")
      (node (ref "U5") (pin "11") (pinfunction "~{INT}_11") (pintype "bidirectional"))
    )
    (net (code "131") (name "unconnected-(U12-5V-Pad+5V)") (class "Default")
      (node (ref "U12") (pin "+5V") (pinfunction "5V_+5V") (pintype "bidirectional"))
    )
    (net (code "132") (name "unconnected-(U12-PadAREF)") (class "Default")
      (node (ref "U12") (pin "AREF") (pinfunction "AREF_AREF") (pintype "bidirectional"))
    )
    (net (code "133") (name "unconnected-(U12-PadVIN)") (class "Default")
      (node (ref "U12") (pin "VIN") (pinfunction "VIN_VIN") (pintype "bidirectional"))
    )
    (net (code "134") (name "~{BAT1_CE}") (class "Default")
      (node (ref "R12") (pin "1") (pinfunction "1_1") (pintype "passive"))
      (node (ref "SYSTEM") (pin "P$5") (pinfunction "5_P$5") (pintype "passive"))
      (node (ref "U12") (pin "D2") (pinfunction "D2_D2") (pintype "bidirectional"))
    )
    (net (code "135") (name "~{BAT2_CE}") (class "Default")
      (node (ref "R19") (pin "1") (pinfunction "1_1") (pintype "passive"))
      (node (ref "SYSTEM") (pin "P$6") (pinfunction "6_P$6") (pintype "passive"))
      (node (ref "U12") (pin "D3") (pinfunction "D3_D3") (pintype "bidirectional"))
    )
    (net (code "136") (name "~{I2C_RST}") (class "Default")
      (node (ref "R58") (pin "2") (pinfunction "2_2") (pintype "passive"))
      (node (ref "SYSTEM") (pin "P$10") (pinfunction "10_P$10") (pintype "passive"))
      (node (ref "U12") (pin "D1") (pinfunction "D1_D1") (pintype "bidirectional"))
      (node (ref "U5") (pin "3") (pinfunction "RST_3") (pintype "bidirectional"))
    )
  )
)
